# Schematic.net
KiCad netlist of a schematic drawn in Altium Designer
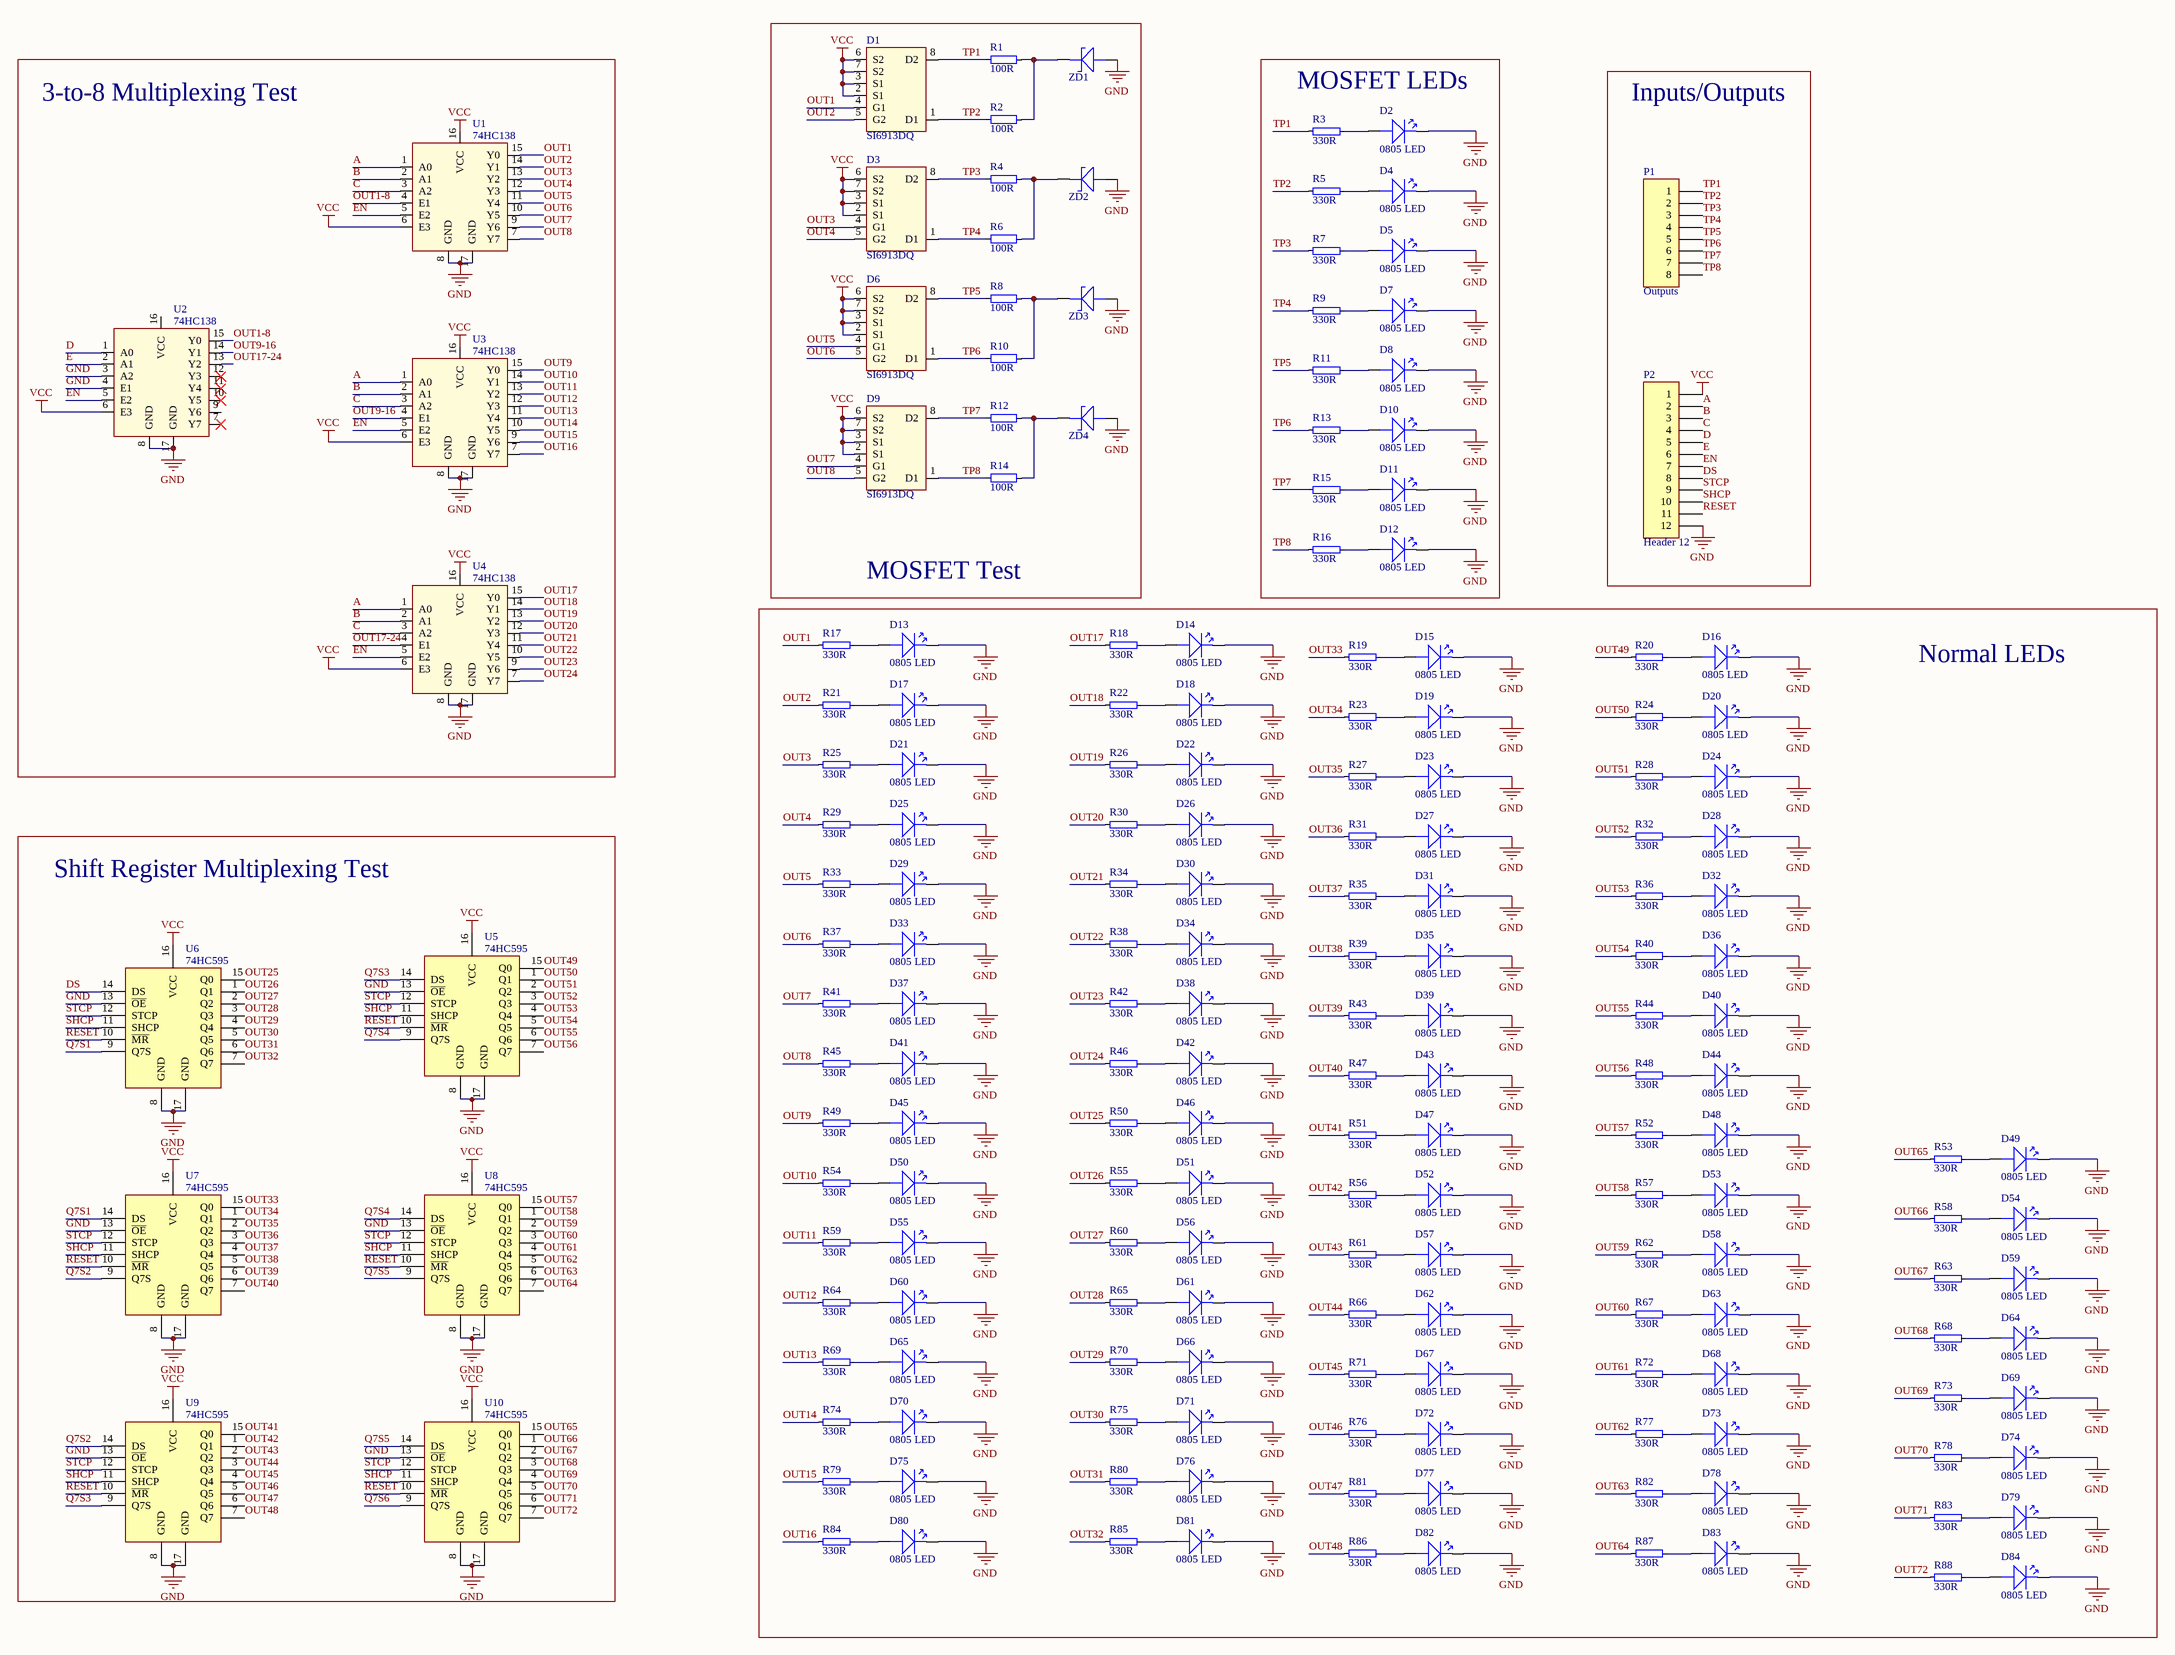
[diagram p0: Schematic.SchDoc]

(export (version "E")
  (design (tool "Eeschema 10.0.6"))
  (components
    (comp (ref "D1")
      (value "SI6913DQ")
      (footprint "Dual Mosfet")
      (libsource (lib "Schlib1") (part "SI6913DQ"))
    )
    (comp (ref "D2") (value "0805 LED") (footprint "0805 LED") (libsource (lib "Schlib1") (part "0805 LED")))
    (comp (ref "D3")
      (value "SI6913DQ")
      (footprint "Dual Mosfet")
      (libsource (lib "Schlib1") (part "SI6913DQ"))
    )
    (comp (ref "D4") (value "0805 LED") (footprint "0805 LED") (libsource (lib "Schlib1") (part "0805 LED")))
    (comp (ref "D5") (value "0805 LED") (footprint "0805 LED") (libsource (lib "Schlib1") (part "0805 LED")))
    (comp (ref "D6")
      (value "SI6913DQ")
      (footprint "Dual Mosfet")
      (libsource (lib "Schlib1") (part "SI6913DQ"))
    )
    (comp (ref "D7") (value "0805 LED") (footprint "0805 LED") (libsource (lib "Schlib1") (part "0805 LED")))
    (comp (ref "D8") (value "0805 LED") (footprint "0805 LED") (libsource (lib "Schlib1") (part "0805 LED")))
    (comp (ref "D9")
      (value "SI6913DQ")
      (footprint "Dual Mosfet")
      (libsource (lib "Schlib1") (part "SI6913DQ"))
    )
    (comp (ref "D10") (value "0805 LED") (footprint "0805 LED") (libsource (lib "Schlib1") (part "0805 LED")))
    (comp (ref "D11") (value "0805 LED") (footprint "0805 LED") (libsource (lib "Schlib1") (part "0805 LED")))
    (comp (ref "D12") (value "0805 LED") (footprint "0805 LED") (libsource (lib "Schlib1") (part "0805 LED")))
    (comp (ref "D13") (value "0805 LED") (footprint "0805 LED") (libsource (lib "Schlib1") (part "0805 LED")))
    (comp (ref "D14") (value "0805 LED") (footprint "0805 LED") (libsource (lib "Schlib1") (part "0805 LED")))
    (comp (ref "D15") (value "0805 LED") (footprint "0805 LED") (libsource (lib "Schlib1") (part "0805 LED")))
    (comp (ref "D16") (value "0805 LED") (footprint "0805 LED") (libsource (lib "Schlib1") (part "0805 LED")))
    (comp (ref "D17") (value "0805 LED") (footprint "0805 LED") (libsource (lib "Schlib1") (part "0805 LED")))
    (comp (ref "D18") (value "0805 LED") (footprint "0805 LED") (libsource (lib "Schlib1") (part "0805 LED")))
    (comp (ref "D19") (value "0805 LED") (footprint "0805 LED") (libsource (lib "Schlib1") (part "0805 LED")))
    (comp (ref "D20") (value "0805 LED") (footprint "0805 LED") (libsource (lib "Schlib1") (part "0805 LED")))
    (comp (ref "D21") (value "0805 LED") (footprint "0805 LED") (libsource (lib "Schlib1") (part "0805 LED")))
    (comp (ref "D22") (value "0805 LED") (footprint "0805 LED") (libsource (lib "Schlib1") (part "0805 LED")))
    (comp (ref "D23") (value "0805 LED") (footprint "0805 LED") (libsource (lib "Schlib1") (part "0805 LED")))
    (comp (ref "D24") (value "0805 LED") (footprint "0805 LED") (libsource (lib "Schlib1") (part "0805 LED")))
    (comp (ref "D25") (value "0805 LED") (footprint "0805 LED") (libsource (lib "Schlib1") (part "0805 LED")))
    (comp (ref "D26") (value "0805 LED") (footprint "0805 LED") (libsource (lib "Schlib1") (part "0805 LED")))
    (comp (ref "D27") (value "0805 LED") (footprint "0805 LED") (libsource (lib "Schlib1") (part "0805 LED")))
    (comp (ref "D28") (value "0805 LED") (footprint "0805 LED") (libsource (lib "Schlib1") (part "0805 LED")))
    (comp (ref "D29") (value "0805 LED") (footprint "0805 LED") (libsource (lib "Schlib1") (part "0805 LED")))
    (comp (ref "D30") (value "0805 LED") (footprint "0805 LED") (libsource (lib "Schlib1") (part "0805 LED")))
    (comp (ref "D31") (value "0805 LED") (footprint "0805 LED") (libsource (lib "Schlib1") (part "0805 LED")))
    (comp (ref "D32") (value "0805 LED") (footprint "0805 LED") (libsource (lib "Schlib1") (part "0805 LED")))
    (comp (ref "D33") (value "0805 LED") (footprint "0805 LED") (libsource (lib "Schlib1") (part "0805 LED")))
    (comp (ref "D34") (value "0805 LED") (footprint "0805 LED") (libsource (lib "Schlib1") (part "0805 LED")))
    (comp (ref "D35") (value "0805 LED") (footprint "0805 LED") (libsource (lib "Schlib1") (part "0805 LED")))
    (comp (ref "D36") (value "0805 LED") (footprint "0805 LED") (libsource (lib "Schlib1") (part "0805 LED")))
    (comp (ref "D37") (value "0805 LED") (footprint "0805 LED") (libsource (lib "Schlib1") (part "0805 LED")))
    (comp (ref "D38") (value "0805 LED") (footprint "0805 LED") (libsource (lib "Schlib1") (part "0805 LED")))
    (comp (ref "D39") (value "0805 LED") (footprint "0805 LED") (libsource (lib "Schlib1") (part "0805 LED")))
    (comp (ref "D40") (value "0805 LED") (footprint "0805 LED") (libsource (lib "Schlib1") (part "0805 LED")))
    (comp (ref "D41") (value "0805 LED") (footprint "0805 LED") (libsource (lib "Schlib1") (part "0805 LED")))
    (comp (ref "D42") (value "0805 LED") (footprint "0805 LED") (libsource (lib "Schlib1") (part "0805 LED")))
    (comp (ref "D43") (value "0805 LED") (footprint "0805 LED") (libsource (lib "Schlib1") (part "0805 LED")))
    (comp (ref "D44") (value "0805 LED") (footprint "0805 LED") (libsource (lib "Schlib1") (part "0805 LED")))
    (comp (ref "D45") (value "0805 LED") (footprint "0805 LED") (libsource (lib "Schlib1") (part "0805 LED")))
    (comp (ref "D46") (value "0805 LED") (footprint "0805 LED") (libsource (lib "Schlib1") (part "0805 LED")))
    (comp (ref "D47") (value "0805 LED") (footprint "0805 LED") (libsource (lib "Schlib1") (part "0805 LED")))
    (comp (ref "D48") (value "0805 LED") (footprint "0805 LED") (libsource (lib "Schlib1") (part "0805 LED")))
    (comp (ref "D49") (value "0805 LED") (footprint "0805 LED") (libsource (lib "Schlib1") (part "0805 LED")))
    (comp (ref "D50") (value "0805 LED") (footprint "0805 LED") (libsource (lib "Schlib1") (part "0805 LED")))
    (comp (ref "D51") (value "0805 LED") (footprint "0805 LED") (libsource (lib "Schlib1") (part "0805 LED")))
    (comp (ref "D52") (value "0805 LED") (footprint "0805 LED") (libsource (lib "Schlib1") (part "0805 LED")))
    (comp (ref "D53") (value "0805 LED") (footprint "0805 LED") (libsource (lib "Schlib1") (part "0805 LED")))
    (comp (ref "D54") (value "0805 LED") (footprint "0805 LED") (libsource (lib "Schlib1") (part "0805 LED")))
    (comp (ref "D55") (value "0805 LED") (footprint "0805 LED") (libsource (lib "Schlib1") (part "0805 LED")))
    (comp (ref "D56") (value "0805 LED") (footprint "0805 LED") (libsource (lib "Schlib1") (part "0805 LED")))
    (comp (ref "D57") (value "0805 LED") (footprint "0805 LED") (libsource (lib "Schlib1") (part "0805 LED")))
    (comp (ref "D58") (value "0805 LED") (footprint "0805 LED") (libsource (lib "Schlib1") (part "0805 LED")))
    (comp (ref "D59") (value "0805 LED") (footprint "0805 LED") (libsource (lib "Schlib1") (part "0805 LED")))
    (comp (ref "D60") (value "0805 LED") (footprint "0805 LED") (libsource (lib "Schlib1") (part "0805 LED")))
    (comp (ref "D61") (value "0805 LED") (footprint "0805 LED") (libsource (lib "Schlib1") (part "0805 LED")))
    (comp (ref "D62") (value "0805 LED") (footprint "0805 LED") (libsource (lib "Schlib1") (part "0805 LED")))
    (comp (ref "D63") (value "0805 LED") (footprint "0805 LED") (libsource (lib "Schlib1") (part "0805 LED")))
    (comp (ref "D64") (value "0805 LED") (footprint "0805 LED") (libsource (lib "Schlib1") (part "0805 LED")))
    (comp (ref "D65") (value "0805 LED") (footprint "0805 LED") (libsource (lib "Schlib1") (part "0805 LED")))
    (comp (ref "D66") (value "0805 LED") (footprint "0805 LED") (libsource (lib "Schlib1") (part "0805 LED")))
    (comp (ref "D67") (value "0805 LED") (footprint "0805 LED") (libsource (lib "Schlib1") (part "0805 LED")))
    (comp (ref "D68") (value "0805 LED") (footprint "0805 LED") (libsource (lib "Schlib1") (part "0805 LED")))
    (comp (ref "D69") (value "0805 LED") (footprint "0805 LED") (libsource (lib "Schlib1") (part "0805 LED")))
    (comp (ref "D70") (value "0805 LED") (footprint "0805 LED") (libsource (lib "Schlib1") (part "0805 LED")))
    (comp (ref "D71") (value "0805 LED") (footprint "0805 LED") (libsource (lib "Schlib1") (part "0805 LED")))
    (comp (ref "D72") (value "0805 LED") (footprint "0805 LED") (libsource (lib "Schlib1") (part "0805 LED")))
    (comp (ref "D73") (value "0805 LED") (footprint "0805 LED") (libsource (lib "Schlib1") (part "0805 LED")))
    (comp (ref "D74") (value "0805 LED") (footprint "0805 LED") (libsource (lib "Schlib1") (part "0805 LED")))
    (comp (ref "D75") (value "0805 LED") (footprint "0805 LED") (libsource (lib "Schlib1") (part "0805 LED")))
    (comp (ref "D76") (value "0805 LED") (footprint "0805 LED") (libsource (lib "Schlib1") (part "0805 LED")))
    (comp (ref "D77") (value "0805 LED") (footprint "0805 LED") (libsource (lib "Schlib1") (part "0805 LED")))
    (comp (ref "D78") (value "0805 LED") (footprint "0805 LED") (libsource (lib "Schlib1") (part "0805 LED")))
    (comp (ref "D79") (value "0805 LED") (footprint "0805 LED") (libsource (lib "Schlib1") (part "0805 LED")))
    (comp (ref "D80") (value "0805 LED") (footprint "0805 LED") (libsource (lib "Schlib1") (part "0805 LED")))
    (comp (ref "D81") (value "0805 LED") (footprint "0805 LED") (libsource (lib "Schlib1") (part "0805 LED")))
    (comp (ref "D82") (value "0805 LED") (footprint "0805 LED") (libsource (lib "Schlib1") (part "0805 LED")))
    (comp (ref "D83") (value "0805 LED") (footprint "0805 LED") (libsource (lib "Schlib1") (part "0805 LED")))
    (comp (ref "D84") (value "0805 LED") (footprint "0805 LED") (libsource (lib "Schlib1") (part "0805 LED")))
    (comp (ref "P1")
      (value "Outputs")
      (footprint "HDR1X8")
      (description "Header, 8-Pin")
      (fields (field (name "PUBLISHER") "Altium Limited"))
      (libsource (lib "Miscellaneous Connectors") (part "Header 8"))
    )
    (comp (ref "P2")
      (value "Header 12")
      (footprint "HDR1X12")
      (description "Header, 12-Pin")
      (fields (field (name "PUBLISHER") "Altium Limited"))
      (libsource (lib "Miscellaneous Connectors") (part "Header 12"))
    )
    (comp (ref "R1")
      (value "100R")
      (footprint "0805 Resistor")
      (libsource (lib "Schlib1") (part "0805 Resistor"))
    )
    (comp (ref "R2")
      (value "100R")
      (footprint "0805 Resistor")
      (libsource (lib "Schlib1") (part "0805 Resistor"))
    )
    (comp (ref "R3")
      (value "330R")
      (footprint "0805 Resistor")
      (libsource (lib "Schlib1") (part "0805 Resistor"))
    )
    (comp (ref "R4")
      (value "100R")
      (footprint "0805 Resistor")
      (libsource (lib "Schlib1") (part "0805 Resistor"))
    )
    (comp (ref "R5")
      (value "330R")
      (footprint "0805 Resistor")
      (libsource (lib "Schlib1") (part "0805 Resistor"))
    )
    (comp (ref "R6")
      (value "100R")
      (footprint "0805 Resistor")
      (libsource (lib "Schlib1") (part "0805 Resistor"))
    )
    (comp (ref "R7")
      (value "330R")
      (footprint "0805 Resistor")
      (libsource (lib "Schlib1") (part "0805 Resistor"))
    )
    (comp (ref "R8")
      (value "100R")
      (footprint "0805 Resistor")
      (libsource (lib "Schlib1") (part "0805 Resistor"))
    )
    (comp (ref "R9")
      (value "330R")
      (footprint "0805 Resistor")
      (libsource (lib "Schlib1") (part "0805 Resistor"))
    )
    (comp (ref "R10")
      (value "100R")
      (footprint "0805 Resistor")
      (libsource (lib "Schlib1") (part "0805 Resistor"))
    )
    (comp (ref "R11")
      (value "330R")
      (footprint "0805 Resistor")
      (libsource (lib "Schlib1") (part "0805 Resistor"))
    )
    (comp (ref "R12")
      (value "100R")
      (footprint "0805 Resistor")
      (libsource (lib "Schlib1") (part "0805 Resistor"))
    )
    (comp (ref "R13")
      (value "330R")
      (footprint "0805 Resistor")
      (libsource (lib "Schlib1") (part "0805 Resistor"))
    )
    (comp (ref "R14")
      (value "100R")
      (footprint "0805 Resistor")
      (libsource (lib "Schlib1") (part "0805 Resistor"))
    )
    (comp (ref "R15")
      (value "330R")
      (footprint "0805 Resistor")
      (libsource (lib "Schlib1") (part "0805 Resistor"))
    )
    (comp (ref "R16")
      (value "330R")
      (footprint "0805 Resistor")
      (libsource (lib "Schlib1") (part "0805 Resistor"))
    )
    (comp (ref "R17")
      (value "330R")
      (footprint "0805 Resistor")
      (libsource (lib "Schlib1") (part "0805 Resistor"))
    )
    (comp (ref "R18")
      (value "330R")
      (footprint "0805 Resistor")
      (libsource (lib "Schlib1") (part "0805 Resistor"))
    )
    (comp (ref "R19")
      (value "330R")
      (footprint "0805 Resistor")
      (libsource (lib "Schlib1") (part "0805 Resistor"))
    )
    (comp (ref "R20")
      (value "330R")
      (footprint "0805 Resistor")
      (libsource (lib "Schlib1") (part "0805 Resistor"))
    )
    (comp (ref "R21")
      (value "330R")
      (footprint "0805 Resistor")
      (libsource (lib "Schlib1") (part "0805 Resistor"))
    )
    (comp (ref "R22")
      (value "330R")
      (footprint "0805 Resistor")
      (libsource (lib "Schlib1") (part "0805 Resistor"))
    )
    (comp (ref "R23")
      (value "330R")
      (footprint "0805 Resistor")
      (libsource (lib "Schlib1") (part "0805 Resistor"))
    )
    (comp (ref "R24")
      (value "330R")
      (footprint "0805 Resistor")
      (libsource (lib "Schlib1") (part "0805 Resistor"))
    )
    (comp (ref "R25")
      (value "330R")
      (footprint "0805 Resistor")
      (libsource (lib "Schlib1") (part "0805 Resistor"))
    )
    (comp (ref "R26")
      (value "330R")
      (footprint "0805 Resistor")
      (libsource (lib "Schlib1") (part "0805 Resistor"))
    )
    (comp (ref "R27")
      (value "330R")
      (footprint "0805 Resistor")
      (libsource (lib "Schlib1") (part "0805 Resistor"))
    )
    (comp (ref "R28")
      (value "330R")
      (footprint "0805 Resistor")
      (libsource (lib "Schlib1") (part "0805 Resistor"))
    )
    (comp (ref "R29")
      (value "330R")
      (footprint "0805 Resistor")
      (libsource (lib "Schlib1") (part "0805 Resistor"))
    )
    (comp (ref "R30")
      (value "330R")
      (footprint "0805 Resistor")
      (libsource (lib "Schlib1") (part "0805 Resistor"))
    )
    (comp (ref "R31")
      (value "330R")
      (footprint "0805 Resistor")
      (libsource (lib "Schlib1") (part "0805 Resistor"))
    )
    (comp (ref "R32")
      (value "330R")
      (footprint "0805 Resistor")
      (libsource (lib "Schlib1") (part "0805 Resistor"))
    )
    (comp (ref "R33")
      (value "330R")
      (footprint "0805 Resistor")
      (libsource (lib "Schlib1") (part "0805 Resistor"))
    )
    (comp (ref "R34")
      (value "330R")
      (footprint "0805 Resistor")
      (libsource (lib "Schlib1") (part "0805 Resistor"))
    )
    (comp (ref "R35")
      (value "330R")
      (footprint "0805 Resistor")
      (libsource (lib "Schlib1") (part "0805 Resistor"))
    )
    (comp (ref "R36")
      (value "330R")
      (footprint "0805 Resistor")
      (libsource (lib "Schlib1") (part "0805 Resistor"))
    )
    (comp (ref "R37")
      (value "330R")
      (footprint "0805 Resistor")
      (libsource (lib "Schlib1") (part "0805 Resistor"))
    )
    (comp (ref "R38")
      (value "330R")
      (footprint "0805 Resistor")
      (libsource (lib "Schlib1") (part "0805 Resistor"))
    )
    (comp (ref "R39")
      (value "330R")
      (footprint "0805 Resistor")
      (libsource (lib "Schlib1") (part "0805 Resistor"))
    )
    (comp (ref "R40")
      (value "330R")
      (footprint "0805 Resistor")
      (libsource (lib "Schlib1") (part "0805 Resistor"))
    )
    (comp (ref "R41")
      (value "330R")
      (footprint "0805 Resistor")
      (libsource (lib "Schlib1") (part "0805 Resistor"))
    )
    (comp (ref "R42")
      (value "330R")
      (footprint "0805 Resistor")
      (libsource (lib "Schlib1") (part "0805 Resistor"))
    )
    (comp (ref "R43")
      (value "330R")
      (footprint "0805 Resistor")
      (libsource (lib "Schlib1") (part "0805 Resistor"))
    )
    (comp (ref "R44")
      (value "330R")
      (footprint "0805 Resistor")
      (libsource (lib "Schlib1") (part "0805 Resistor"))
    )
    (comp (ref "R45")
      (value "330R")
      (footprint "0805 Resistor")
      (libsource (lib "Schlib1") (part "0805 Resistor"))
    )
    (comp (ref "R46")
      (value "330R")
      (footprint "0805 Resistor")
      (libsource (lib "Schlib1") (part "0805 Resistor"))
    )
    (comp (ref "R47")
      (value "330R")
      (footprint "0805 Resistor")
      (libsource (lib "Schlib1") (part "0805 Resistor"))
    )
    (comp (ref "R48")
      (value "330R")
      (footprint "0805 Resistor")
      (libsource (lib "Schlib1") (part "0805 Resistor"))
    )
    (comp (ref "R49")
      (value "330R")
      (footprint "0805 Resistor")
      (libsource (lib "Schlib1") (part "0805 Resistor"))
    )
    (comp (ref "R50")
      (value "330R")
      (footprint "0805 Resistor")
      (libsource (lib "Schlib1") (part "0805 Resistor"))
    )
    (comp (ref "R51")
      (value "330R")
      (footprint "0805 Resistor")
      (libsource (lib "Schlib1") (part "0805 Resistor"))
    )
    (comp (ref "R52")
      (value "330R")
      (footprint "0805 Resistor")
      (libsource (lib "Schlib1") (part "0805 Resistor"))
    )
    (comp (ref "R53")
      (value "330R")
      (footprint "0805 Resistor")
      (libsource (lib "Schlib1") (part "0805 Resistor"))
    )
    (comp (ref "R54")
      (value "330R")
      (footprint "0805 Resistor")
      (libsource (lib "Schlib1") (part "0805 Resistor"))
    )
    (comp (ref "R55")
      (value "330R")
      (footprint "0805 Resistor")
      (libsource (lib "Schlib1") (part "0805 Resistor"))
    )
    (comp (ref "R56")
      (value "330R")
      (footprint "0805 Resistor")
      (libsource (lib "Schlib1") (part "0805 Resistor"))
    )
    (comp (ref "R57")
      (value "330R")
      (footprint "0805 Resistor")
      (libsource (lib "Schlib1") (part "0805 Resistor"))
    )
    (comp (ref "R58")
      (value "330R")
      (footprint "0805 Resistor")
      (libsource (lib "Schlib1") (part "0805 Resistor"))
    )
    (comp (ref "R59")
      (value "330R")
      (footprint "0805 Resistor")
      (libsource (lib "Schlib1") (part "0805 Resistor"))
    )
    (comp (ref "R60")
      (value "330R")
      (footprint "0805 Resistor")
      (libsource (lib "Schlib1") (part "0805 Resistor"))
    )
    (comp (ref "R61")
      (value "330R")
      (footprint "0805 Resistor")
      (libsource (lib "Schlib1") (part "0805 Resistor"))
    )
    (comp (ref "R62")
      (value "330R")
      (footprint "0805 Resistor")
      (libsource (lib "Schlib1") (part "0805 Resistor"))
    )
    (comp (ref "R63")
      (value "330R")
      (footprint "0805 Resistor")
      (libsource (lib "Schlib1") (part "0805 Resistor"))
    )
    (comp (ref "R64")
      (value "330R")
      (footprint "0805 Resistor")
      (libsource (lib "Schlib1") (part "0805 Resistor"))
    )
    (comp (ref "R65")
      (value "330R")
      (footprint "0805 Resistor")
      (libsource (lib "Schlib1") (part "0805 Resistor"))
    )
    (comp (ref "R66")
      (value "330R")
      (footprint "0805 Resistor")
      (libsource (lib "Schlib1") (part "0805 Resistor"))
    )
    (comp (ref "R67")
      (value "330R")
      (footprint "0805 Resistor")
      (libsource (lib "Schlib1") (part "0805 Resistor"))
    )
    (comp (ref "R68")
      (value "330R")
      (footprint "0805 Resistor")
      (libsource (lib "Schlib1") (part "0805 Resistor"))
    )
    (comp (ref "R69")
      (value "330R")
      (footprint "0805 Resistor")
      (libsource (lib "Schlib1") (part "0805 Resistor"))
    )
    (comp (ref "R70")
      (value "330R")
      (footprint "0805 Resistor")
      (libsource (lib "Schlib1") (part "0805 Resistor"))
    )
    (comp (ref "R71")
      (value "330R")
      (footprint "0805 Resistor")
      (libsource (lib "Schlib1") (part "0805 Resistor"))
    )
    (comp (ref "R72")
      (value "330R")
      (footprint "0805 Resistor")
      (libsource (lib "Schlib1") (part "0805 Resistor"))
    )
    (comp (ref "R73")
      (value "330R")
      (footprint "0805 Resistor")
      (libsource (lib "Schlib1") (part "0805 Resistor"))
    )
    (comp (ref "R74")
      (value "330R")
      (footprint "0805 Resistor")
      (libsource (lib "Schlib1") (part "0805 Resistor"))
    )
    (comp (ref "R75")
      (value "330R")
      (footprint "0805 Resistor")
      (libsource (lib "Schlib1") (part "0805 Resistor"))
    )
    (comp (ref "R76")
      (value "330R")
      (footprint "0805 Resistor")
      (libsource (lib "Schlib1") (part "0805 Resistor"))
    )
    (comp (ref "R77")
      (value "330R")
      (footprint "0805 Resistor")
      (libsource (lib "Schlib1") (part "0805 Resistor"))
    )
    (comp (ref "R78")
      (value "330R")
      (footprint "0805 Resistor")
      (libsource (lib "Schlib1") (part "0805 Resistor"))
    )
    (comp (ref "R79")
      (value "330R")
      (footprint "0805 Resistor")
      (libsource (lib "Schlib1") (part "0805 Resistor"))
    )
    (comp (ref "R80")
      (value "330R")
      (footprint "0805 Resistor")
      (libsource (lib "Schlib1") (part "0805 Resistor"))
    )
    (comp (ref "R81")
      (value "330R")
      (footprint "0805 Resistor")
      (libsource (lib "Schlib1") (part "0805 Resistor"))
    )
    (comp (ref "R82")
      (value "330R")
      (footprint "0805 Resistor")
      (libsource (lib "Schlib1") (part "0805 Resistor"))
    )
    (comp (ref "R83")
      (value "330R")
      (footprint "0805 Resistor")
      (libsource (lib "Schlib1") (part "0805 Resistor"))
    )
    (comp (ref "R84")
      (value "330R")
      (footprint "0805 Resistor")
      (libsource (lib "Schlib1") (part "0805 Resistor"))
    )
    (comp (ref "R85")
      (value "330R")
      (footprint "0805 Resistor")
      (libsource (lib "Schlib1") (part "0805 Resistor"))
    )
    (comp (ref "R86")
      (value "330R")
      (footprint "0805 Resistor")
      (libsource (lib "Schlib1") (part "0805 Resistor"))
    )
    (comp (ref "R87")
      (value "330R")
      (footprint "0805 Resistor")
      (libsource (lib "Schlib1") (part "0805 Resistor"))
    )
    (comp (ref "R88")
      (value "330R")
      (footprint "0805 Resistor")
      (libsource (lib "Schlib1") (part "0805 Resistor"))
    )
    (comp (ref "U1") (value "74HC138") (footprint "74HC595") (libsource (lib "Schlib1") (part "74HC138")))
    (comp (ref "U2") (value "74HC138") (footprint "74HC595") (libsource (lib "Schlib1") (part "74HC138")))
    (comp (ref "U3") (value "74HC138") (footprint "74HC595") (libsource (lib "Schlib1") (part "74HC138")))
    (comp (ref "U4") (value "74HC138") (footprint "74HC595") (libsource (lib "Schlib1") (part "74HC138")))
    (comp (ref "U5") (value "74HC595") (footprint "74HC595") (libsource (lib "Schlib1") (part "74HC595")))
    (comp (ref "U6") (value "74HC595") (footprint "74HC595") (libsource (lib "Schlib1") (part "74HC595")))
    (comp (ref "U7") (value "74HC595") (footprint "74HC595") (libsource (lib "Schlib1") (part "74HC595")))
    (comp (ref "U8") (value "74HC595") (footprint "74HC595") (libsource (lib "Schlib1") (part "74HC595")))
    (comp (ref "U9") (value "74HC595") (footprint "74HC595") (libsource (lib "Schlib1") (part "74HC595")))
    (comp (ref "U10") (value "74HC595") (footprint "74HC595") (libsource (lib "Schlib1") (part "74HC595")))
    (comp (ref "ZD1") (value "3V") (footprint "Zener Diode") (libsource (lib "Schlib1") (part "BZV55-C3V0")))
    (comp (ref "ZD2") (value "3V") (footprint "Zener Diode") (libsource (lib "Schlib1") (part "BZV55-C3V0")))
    (comp (ref "ZD3") (value "3V") (footprint "Zener Diode") (libsource (lib "Schlib1") (part "BZV55-C3V0")))
    (comp (ref "ZD4") (value "3V") (footprint "Zener Diode") (libsource (lib "Schlib1") (part "BZV55-C3V0")))
  )
  (nets
    (net (code "1") (name "/A") (class "Default")
      (node (ref "P2") (pin "2") (pinfunction "2_2") (pintype "passive"))
      (node (ref "U1") (pin "1") (pinfunction "A0_1") (pintype "passive"))
      (node (ref "U3") (pin "1") (pinfunction "A0_1") (pintype "passive"))
      (node (ref "U4") (pin "1") (pinfunction "A0_1") (pintype "passive"))
    )
    (net (code "2") (name "/B") (class "Default")
      (node (ref "P2") (pin "3") (pinfunction "3_3") (pintype "passive"))
      (node (ref "U1") (pin "2") (pinfunction "A1_2") (pintype "passive"))
      (node (ref "U3") (pin "2") (pinfunction "A1_2") (pintype "passive"))
      (node (ref "U4") (pin "2") (pinfunction "A1_2") (pintype "passive"))
    )
    (net (code "3") (name "/C") (class "Default")
      (node (ref "P2") (pin "4") (pinfunction "4_4") (pintype "passive"))
      (node (ref "U1") (pin "3") (pinfunction "A2_3") (pintype "passive"))
      (node (ref "U3") (pin "3") (pinfunction "A2_3") (pintype "passive"))
      (node (ref "U4") (pin "3") (pinfunction "A2_3") (pintype "passive"))
    )
    (net (code "4") (name "/D") (class "Default")
      (node (ref "P2") (pin "5") (pinfunction "5_5") (pintype "passive"))
      (node (ref "U2") (pin "1") (pinfunction "A0_1") (pintype "passive"))
    )
    (net (code "5") (name "/DS") (class "Default")
      (node (ref "P2") (pin "8") (pinfunction "8_8") (pintype "passive"))
      (node (ref "U6") (pin "14") (pinfunction "DS_14") (pintype "passive"))
    )
    (net (code "6") (name "/E") (class "Default")
      (node (ref "P2") (pin "6") (pinfunction "6_6") (pintype "passive"))
      (node (ref "U2") (pin "2") (pinfunction "A1_2") (pintype "passive"))
    )
    (net (code "7") (name "/EN") (class "Default")
      (node (ref "P2") (pin "7") (pinfunction "7_7") (pintype "passive"))
      (node (ref "U1") (pin "5") (pinfunction "E2_5") (pintype "passive"))
      (node (ref "U2") (pin "5") (pinfunction "E2_5") (pintype "passive"))
      (node (ref "U3") (pin "5") (pinfunction "E2_5") (pintype "passive"))
      (node (ref "U4") (pin "5") (pinfunction "E2_5") (pintype "passive"))
    )
    (net (code "8") (name "/OUT1") (class "Default")
      (node (ref "D1") (pin "4") (pinfunction "G1_4") (pintype "passive"))
      (node (ref "R17") (pin "2") (pinfunction "2_2") (pintype "passive"))
      (node (ref "U1") (pin "15") (pinfunction "Y0_15") (pintype "passive"))
    )
    (net (code "9") (name "/OUT1-8") (class "Default")
      (node (ref "U1") (pin "4") (pinfunction "E1_4") (pintype "passive"))
      (node (ref "U2") (pin "15") (pinfunction "Y0_15") (pintype "passive"))
    )
    (net (code "10") (name "/OUT2") (class "Default")
      (node (ref "D1") (pin "5") (pinfunction "G2_5") (pintype "passive"))
      (node (ref "R21") (pin "2") (pinfunction "2_2") (pintype "passive"))
      (node (ref "U1") (pin "14") (pinfunction "Y1_14") (pintype "passive"))
    )
    (net (code "11") (name "/OUT3") (class "Default")
      (node (ref "D3") (pin "4") (pinfunction "G1_4") (pintype "passive"))
      (node (ref "R25") (pin "2") (pinfunction "2_2") (pintype "passive"))
      (node (ref "U1") (pin "13") (pinfunction "Y2_13") (pintype "passive"))
    )
    (net (code "12") (name "/OUT4") (class "Default")
      (node (ref "D3") (pin "5") (pinfunction "G2_5") (pintype "passive"))
      (node (ref "R29") (pin "2") (pinfunction "2_2") (pintype "passive"))
      (node (ref "U1") (pin "12") (pinfunction "Y3_12") (pintype "passive"))
    )
    (net (code "13") (name "/OUT5") (class "Default")
      (node (ref "D6") (pin "4") (pinfunction "G1_4") (pintype "passive"))
      (node (ref "R33") (pin "2") (pinfunction "2_2") (pintype "passive"))
      (node (ref "U1") (pin "11") (pinfunction "Y4_11") (pintype "passive"))
    )
    (net (code "14") (name "/OUT6") (class "Default")
      (node (ref "D6") (pin "5") (pinfunction "G2_5") (pintype "passive"))
      (node (ref "R37") (pin "2") (pinfunction "2_2") (pintype "passive"))
      (node (ref "U1") (pin "10") (pinfunction "Y5_10") (pintype "passive"))
    )
    (net (code "15") (name "/OUT7") (class "Default")
      (node (ref "D9") (pin "4") (pinfunction "G1_4") (pintype "passive"))
      (node (ref "R41") (pin "2") (pinfunction "2_2") (pintype "passive"))
      (node (ref "U1") (pin "9") (pinfunction "Y6_9") (pintype "passive"))
    )
    (net (code "16") (name "/OUT8") (class "Default")
      (node (ref "D9") (pin "5") (pinfunction "G2_5") (pintype "passive"))
      (node (ref "R45") (pin "2") (pinfunction "2_2") (pintype "passive"))
      (node (ref "U1") (pin "7") (pinfunction "Y7_7") (pintype "passive"))
    )
    (net (code "17") (name "/OUT9") (class "Default")
      (node (ref "R49") (pin "2") (pinfunction "2_2") (pintype "passive"))
      (node (ref "U3") (pin "15") (pinfunction "Y0_15") (pintype "passive"))
    )
    (net (code "18") (name "/OUT9-16") (class "Default")
      (node (ref "U2") (pin "14") (pinfunction "Y1_14") (pintype "passive"))
      (node (ref "U3") (pin "4") (pinfunction "E1_4") (pintype "passive"))
    )
    (net (code "19") (name "/OUT10") (class "Default")
      (node (ref "R54") (pin "2") (pinfunction "2_2") (pintype "passive"))
      (node (ref "U3") (pin "14") (pinfunction "Y1_14") (pintype "passive"))
    )
    (net (code "20") (name "/OUT11") (class "Default")
      (node (ref "R59") (pin "2") (pinfunction "2_2") (pintype "passive"))
      (node (ref "U3") (pin "13") (pinfunction "Y2_13") (pintype "passive"))
    )
    (net (code "21") (name "/OUT12") (class "Default")
      (node (ref "R64") (pin "2") (pinfunction "2_2") (pintype "passive"))
      (node (ref "U3") (pin "12") (pinfunction "Y3_12") (pintype "passive"))
    )
    (net (code "22") (name "/OUT13") (class "Default")
      (node (ref "R69") (pin "2") (pinfunction "2_2") (pintype "passive"))
      (node (ref "U3") (pin "11") (pinfunction "Y4_11") (pintype "passive"))
    )
    (net (code "23") (name "/OUT14") (class "Default")
      (node (ref "R74") (pin "2") (pinfunction "2_2") (pintype "passive"))
      (node (ref "U3") (pin "10") (pinfunction "Y5_10") (pintype "passive"))
    )
    (net (code "24") (name "/OUT15") (class "Default")
      (node (ref "R79") (pin "2") (pinfunction "2_2") (pintype "passive"))
      (node (ref "U3") (pin "9") (pinfunction "Y6_9") (pintype "passive"))
    )
    (net (code "25") (name "/OUT16") (class "Default")
      (node (ref "R84") (pin "2") (pinfunction "2_2") (pintype "passive"))
      (node (ref "U3") (pin "7") (pinfunction "Y7_7") (pintype "passive"))
    )
    (net (code "26") (name "/OUT17") (class "Default")
      (node (ref "R18") (pin "2") (pinfunction "2_2") (pintype "passive"))
      (node (ref "U4") (pin "15") (pinfunction "Y0_15") (pintype "passive"))
    )
    (net (code "27") (name "/OUT17-24") (class "Default")
      (node (ref "U2") (pin "13") (pinfunction "Y2_13") (pintype "passive"))
      (node (ref "U4") (pin "4") (pinfunction "E1_4") (pintype "passive"))
    )
    (net (code "28") (name "/OUT18") (class "Default")
      (node (ref "R22") (pin "2") (pinfunction "2_2") (pintype "passive"))
      (node (ref "U4") (pin "14") (pinfunction "Y1_14") (pintype "passive"))
    )
    (net (code "29") (name "/OUT19") (class "Default")
      (node (ref "R26") (pin "2") (pinfunction "2_2") (pintype "passive"))
      (node (ref "U4") (pin "13") (pinfunction "Y2_13") (pintype "passive"))
    )
    (net (code "30") (name "/OUT20") (class "Default")
      (node (ref "R30") (pin "2") (pinfunction "2_2") (pintype "passive"))
      (node (ref "U4") (pin "12") (pinfunction "Y3_12") (pintype "passive"))
    )
    (net (code "31") (name "/OUT21") (class "Default")
      (node (ref "R34") (pin "2") (pinfunction "2_2") (pintype "passive"))
      (node (ref "U4") (pin "11") (pinfunction "Y4_11") (pintype "passive"))
    )
    (net (code "32") (name "/OUT22") (class "Default")
      (node (ref "R38") (pin "2") (pinfunction "2_2") (pintype "passive"))
      (node (ref "U4") (pin "10") (pinfunction "Y5_10") (pintype "passive"))
    )
    (net (code "33") (name "/OUT23") (class "Default")
      (node (ref "R42") (pin "2") (pinfunction "2_2") (pintype "passive"))
      (node (ref "U4") (pin "9") (pinfunction "Y6_9") (pintype "passive"))
    )
    (net (code "34") (name "/OUT24") (class "Default")
      (node (ref "R46") (pin "2") (pinfunction "2_2") (pintype "passive"))
      (node (ref "U4") (pin "7") (pinfunction "Y7_7") (pintype "passive"))
    )
    (net (code "35") (name "/OUT25") (class "Default")
      (node (ref "R50") (pin "2") (pinfunction "2_2") (pintype "passive"))
      (node (ref "U6") (pin "15") (pinfunction "Q0_15") (pintype "passive"))
    )
    (net (code "36") (name "/OUT26") (class "Default")
      (node (ref "R55") (pin "2") (pinfunction "2_2") (pintype "passive"))
      (node (ref "U6") (pin "1") (pinfunction "Q1_1") (pintype "passive"))
    )
    (net (code "37") (name "/OUT27") (class "Default")
      (node (ref "R60") (pin "2") (pinfunction "2_2") (pintype "passive"))
      (node (ref "U6") (pin "2") (pinfunction "Q2_2") (pintype "passive"))
    )
    (net (code "38") (name "/OUT28") (class "Default")
      (node (ref "R65") (pin "2") (pinfunction "2_2") (pintype "passive"))
      (node (ref "U6") (pin "3") (pinfunction "Q3_3") (pintype "passive"))
    )
    (net (code "39") (name "/OUT29") (class "Default")
      (node (ref "R70") (pin "2") (pinfunction "2_2") (pintype "passive"))
      (node (ref "U6") (pin "4") (pinfunction "Q4_4") (pintype "passive"))
    )
    (net (code "40") (name "/OUT30") (class "Default")
      (node (ref "R75") (pin "2") (pinfunction "2_2") (pintype "passive"))
      (node (ref "U6") (pin "5") (pinfunction "Q5_5") (pintype "passive"))
    )
    (net (code "41") (name "/OUT31") (class "Default")
      (node (ref "R80") (pin "2") (pinfunction "2_2") (pintype "passive"))
      (node (ref "U6") (pin "6") (pinfunction "Q6_6") (pintype "passive"))
    )
    (net (code "42") (name "/OUT32") (class "Default")
      (node (ref "R85") (pin "2") (pinfunction "2_2") (pintype "passive"))
      (node (ref "U6") (pin "7") (pinfunction "Q7_7") (pintype "passive"))
    )
    (net (code "43") (name "/OUT33") (class "Default")
      (node (ref "R19") (pin "2") (pinfunction "2_2") (pintype "passive"))
      (node (ref "U7") (pin "15") (pinfunction "Q0_15") (pintype "passive"))
    )
    (net (code "44") (name "/OUT34") (class "Default")
      (node (ref "R23") (pin "2") (pinfunction "2_2") (pintype "passive"))
      (node (ref "U7") (pin "1") (pinfunction "Q1_1") (pintype "passive"))
    )
    (net (code "45") (name "/OUT35") (class "Default")
      (node (ref "R27") (pin "2") (pinfunction "2_2") (pintype "passive"))
      (node (ref "U7") (pin "2") (pinfunction "Q2_2") (pintype "passive"))
    )
    (net (code "46") (name "/OUT36") (class "Default")
      (node (ref "R31") (pin "2") (pinfunction "2_2") (pintype "passive"))
      (node (ref "U7") (pin "3") (pinfunction "Q3_3") (pintype "passive"))
    )
    (net (code "47") (name "/OUT37") (class "Default")
      (node (ref "R35") (pin "2") (pinfunction "2_2") (pintype "passive"))
      (node (ref "U7") (pin "4") (pinfunction "Q4_4") (pintype "passive"))
    )
    (net (code "48") (name "/OUT38") (class "Default")
      (node (ref "R39") (pin "2") (pinfunction "2_2") (pintype "passive"))
      (node (ref "U7") (pin "5") (pinfunction "Q5_5") (pintype "passive"))
    )
    (net (code "49") (name "/OUT39") (class "Default")
      (node (ref "R43") (pin "2") (pinfunction "2_2") (pintype "passive"))
      (node (ref "U7") (pin "6") (pinfunction "Q6_6") (pintype "passive"))
    )
    (net (code "50") (name "/OUT40") (class "Default")
      (node (ref "R47") (pin "2") (pinfunction "2_2") (pintype "passive"))
      (node (ref "U7") (pin "7") (pinfunction "Q7_7") (pintype "passive"))
    )
    (net (code "51") (name "/OUT41") (class "Default")
      (node (ref "R51") (pin "2") (pinfunction "2_2") (pintype "passive"))
      (node (ref "U9") (pin "15") (pinfunction "Q0_15") (pintype "passive"))
    )
    (net (code "52") (name "/OUT42") (class "Default")
      (node (ref "R56") (pin "2") (pinfunction "2_2") (pintype "passive"))
      (node (ref "U9") (pin "1") (pinfunction "Q1_1") (pintype "passive"))
    )
    (net (code "53") (name "/OUT43") (class "Default")
      (node (ref "R61") (pin "2") (pinfunction "2_2") (pintype "passive"))
      (node (ref "U9") (pin "2") (pinfunction "Q2_2") (pintype "passive"))
    )
    (net (code "54") (name "/OUT44") (class "Default")
      (node (ref "R66") (pin "2") (pinfunction "2_2") (pintype "passive"))
      (node (ref "U9") (pin "3") (pinfunction "Q3_3") (pintype "passive"))
    )
    (net (code "55") (name "/OUT45") (class "Default")
      (node (ref "R71") (pin "2") (pinfunction "2_2") (pintype "passive"))
      (node (ref "U9") (pin "4") (pinfunction "Q4_4") (pintype "passive"))
    )
    (net (code "56") (name "/OUT46") (class "Default")
      (node (ref "R76") (pin "2") (pinfunction "2_2") (pintype "passive"))
      (node (ref "U9") (pin "5") (pinfunction "Q5_5") (pintype "passive"))
    )
    (net (code "57") (name "/OUT47") (class "Default")
      (node (ref "R81") (pin "2") (pinfunction "2_2") (pintype "passive"))
      (node (ref "U9") (pin "6") (pinfunction "Q6_6") (pintype "passive"))
    )
    (net (code "58") (name "/OUT48") (class "Default")
      (node (ref "R86") (pin "2") (pinfunction "2_2") (pintype "passive"))
      (node (ref "U9") (pin "7") (pinfunction "Q7_7") (pintype "passive"))
    )
    (net (code "59") (name "/OUT49") (class "Default")
      (node (ref "R20") (pin "2") (pinfunction "2_2") (pintype "passive"))
      (node (ref "U5") (pin "15") (pinfunction "Q0_15") (pintype "passive"))
    )
    (net (code "60") (name "/OUT50") (class "Default")
      (node (ref "R24") (pin "2") (pinfunction "2_2") (pintype "passive"))
      (node (ref "U5") (pin "1") (pinfunction "Q1_1") (pintype "passive"))
    )
    (net (code "61") (name "/OUT51") (class "Default")
      (node (ref "R28") (pin "2") (pinfunction "2_2") (pintype "passive"))
      (node (ref "U5") (pin "2") (pinfunction "Q2_2") (pintype "passive"))
    )
    (net (code "62") (name "/OUT52") (class "Default")
      (node (ref "R32") (pin "2") (pinfunction "2_2") (pintype "passive"))
      (node (ref "U5") (pin "3") (pinfunction "Q3_3") (pintype "passive"))
    )
    (net (code "63") (name "/OUT53") (class "Default")
      (node (ref "R36") (pin "2") (pinfunction "2_2") (pintype "passive"))
      (node (ref "U5") (pin "4") (pinfunction "Q4_4") (pintype "passive"))
    )
    (net (code "64") (name "/OUT54") (class "Default")
      (node (ref "R40") (pin "2") (pinfunction "2_2") (pintype "passive"))
      (node (ref "U5") (pin "5") (pinfunction "Q5_5") (pintype "passive"))
    )
    (net (code "65") (name "/OUT55") (class "Default")
      (node (ref "R44") (pin "2") (pinfunction "2_2") (pintype "passive"))
      (node (ref "U5") (pin "6") (pinfunction "Q6_6") (pintype "passive"))
    )
    (net (code "66") (name "/OUT56") (class "Default")
      (node (ref "R48") (pin "2") (pinfunction "2_2") (pintype "passive"))
      (node (ref "U5") (pin "7") (pinfunction "Q7_7") (pintype "passive"))
    )
    (net (code "67") (name "/OUT57") (class "Default")
      (node (ref "R52") (pin "2") (pinfunction "2_2") (pintype "passive"))
      (node (ref "U8") (pin "15") (pinfunction "Q0_15") (pintype "passive"))
    )
    (net (code "68") (name "/OUT58") (class "Default")
      (node (ref "R57") (pin "2") (pinfunction "2_2") (pintype "passive"))
      (node (ref "U8") (pin "1") (pinfunction "Q1_1") (pintype "passive"))
    )
    (net (code "69") (name "/OUT59") (class "Default")
      (node (ref "R62") (pin "2") (pinfunction "2_2") (pintype "passive"))
      (node (ref "U8") (pin "2") (pinfunction "Q2_2") (pintype "passive"))
    )
    (net (code "70") (name "/OUT60") (class "Default")
      (node (ref "R67") (pin "2") (pinfunction "2_2") (pintype "passive"))
      (node (ref "U8") (pin "3") (pinfunction "Q3_3") (pintype "passive"))
    )
    (net (code "71") (name "/OUT61") (class "Default")
      (node (ref "R72") (pin "2") (pinfunction "2_2") (pintype "passive"))
      (node (ref "U8") (pin "4") (pinfunction "Q4_4") (pintype "passive"))
    )
    (net (code "72") (name "/OUT62") (class "Default")
      (node (ref "R77") (pin "2") (pinfunction "2_2") (pintype "passive"))
      (node (ref "U8") (pin "5") (pinfunction "Q5_5") (pintype "passive"))
    )
    (net (code "73") (name "/OUT63") (class "Default")
      (node (ref "R82") (pin "2") (pinfunction "2_2") (pintype "passive"))
      (node (ref "U8") (pin "6") (pinfunction "Q6_6") (pintype "passive"))
    )
    (net (code "74") (name "/OUT64") (class "Default")
      (node (ref "R87") (pin "2") (pinfunction "2_2") (pintype "passive"))
      (node (ref "U8") (pin "7") (pinfunction "Q7_7") (pintype "passive"))
    )
    (net (code "75") (name "/OUT65") (class "Default")
      (node (ref "R53") (pin "2") (pinfunction "2_2") (pintype "passive"))
      (node (ref "U10") (pin "15") (pinfunction "Q0_15") (pintype "passive"))
    )
    (net (code "76") (name "/OUT66") (class "Default")
      (node (ref "R58") (pin "2") (pinfunction "2_2") (pintype "passive"))
      (node (ref "U10") (pin "1") (pinfunction "Q1_1") (pintype "passive"))
    )
    (net (code "77") (name "/OUT67") (class "Default")
      (node (ref "R63") (pin "2") (pinfunction "2_2") (pintype "passive"))
      (node (ref "U10") (pin "2") (pinfunction "Q2_2") (pintype "passive"))
    )
    (net (code "78") (name "/OUT68") (class "Default")
      (node (ref "R68") (pin "2") (pinfunction "2_2") (pintype "passive"))
      (node (ref "U10") (pin "3") (pinfunction "Q3_3") (pintype "passive"))
    )
    (net (code "79") (name "/OUT69") (class "Default")
      (node (ref "R73") (pin "2") (pinfunction "2_2") (pintype "passive"))
      (node (ref "U10") (pin "4") (pinfunction "Q4_4") (pintype "passive"))
    )
    (net (code "80") (name "/OUT70") (class "Default")
      (node (ref "R78") (pin "2") (pinfunction "2_2") (pintype "passive"))
      (node (ref "U10") (pin "5") (pinfunction "Q5_5") (pintype "passive"))
    )
    (net (code "81") (name "/OUT71") (class "Default")
      (node (ref "R83") (pin "2") (pinfunction "2_2") (pintype "passive"))
      (node (ref "U10") (pin "6") (pinfunction "Q6_6") (pintype "passive"))
    )
    (net (code "82") (name "/OUT72") (class "Default")
      (node (ref "R88") (pin "2") (pinfunction "2_2") (pintype "passive"))
      (node (ref "U10") (pin "7") (pinfunction "Q7_7") (pintype "passive"))
    )
    (net (code "83") (name "/Q7S1") (class "Default")
      (node (ref "U6") (pin "9") (pinfunction "Q7S_9") (pintype "passive"))
      (node (ref "U7") (pin "14") (pinfunction "DS_14") (pintype "passive"))
    )
    (net (code "84") (name "/Q7S2") (class "Default")
      (node (ref "U7") (pin "9") (pinfunction "Q7S_9") (pintype "passive"))
      (node (ref "U9") (pin "14") (pinfunction "DS_14") (pintype "passive"))
    )
    (net (code "85") (name "/Q7S3") (class "Default")
      (node (ref "U5") (pin "14") (pinfunction "DS_14") (pintype "passive"))
      (node (ref "U9") (pin "9") (pinfunction "Q7S_9") (pintype "passive"))
    )
    (net (code "86") (name "/Q7S4") (class "Default")
      (node (ref "U5") (pin "9") (pinfunction "Q7S_9") (pintype "passive"))
      (node (ref "U8") (pin "14") (pinfunction "DS_14") (pintype "passive"))
    )
    (net (code "87") (name "/Q7S5") (class "Default")
      (node (ref "U10") (pin "14") (pinfunction "DS_14") (pintype "passive"))
      (node (ref "U8") (pin "9") (pinfunction "Q7S_9") (pintype "passive"))
    )
    (net (code "88") (name "/Q7S6") (class "Default")
      (node (ref "U10") (pin "9") (pinfunction "Q7S_9") (pintype "passive"))
    )
    (net (code "89") (name "/RESET") (class "Default")
      (node (ref "P2") (pin "11") (pinfunction "11_11") (pintype "passive"))
      (node (ref "U10") (pin "10") (pinfunction "~{MR}_10") (pintype "passive"))
      (node (ref "U5") (pin "10") (pinfunction "~{MR}_10") (pintype "passive"))
      (node (ref "U6") (pin "10") (pinfunction "~{MR}_10") (pintype "passive"))
      (node (ref "U7") (pin "10") (pinfunction "~{MR}_10") (pintype "passive"))
      (node (ref "U8") (pin "10") (pinfunction "~{MR}_10") (pintype "passive"))
      (node (ref "U9") (pin "10") (pinfunction "~{MR}_10") (pintype "passive"))
    )
    (net (code "90") (name "/SHCP") (class "Default")
      (node (ref "P2") (pin "10") (pinfunction "10_10") (pintype "passive"))
      (node (ref "U10") (pin "11") (pinfunction "SHCP_11") (pintype "passive"))
      (node (ref "U5") (pin "11") (pinfunction "SHCP_11") (pintype "passive"))
      (node (ref "U6") (pin "11") (pinfunction "SHCP_11") (pintype "passive"))
      (node (ref "U7") (pin "11") (pinfunction "SHCP_11") (pintype "passive"))
      (node (ref "U8") (pin "11") (pinfunction "SHCP_11") (pintype "passive"))
      (node (ref "U9") (pin "11") (pinfunction "SHCP_11") (pintype "passive"))
    )
    (net (code "91") (name "/STCP") (class "Default")
      (node (ref "P2") (pin "9") (pinfunction "9_9") (pintype "passive"))
      (node (ref "U10") (pin "12") (pinfunction "STCP_12") (pintype "passive"))
      (node (ref "U5") (pin "12") (pinfunction "STCP_12") (pintype "passive"))
      (node (ref "U6") (pin "12") (pinfunction "STCP_12") (pintype "passive"))
      (node (ref "U7") (pin "12") (pinfunction "STCP_12") (pintype "passive"))
      (node (ref "U8") (pin "12") (pinfunction "STCP_12") (pintype "passive"))
      (node (ref "U9") (pin "12") (pinfunction "STCP_12") (pintype "passive"))
    )
    (net (code "92") (name "/TP1") (class "Default")
      (node (ref "D1") (pin "8") (pinfunction "D2_8") (pintype "passive"))
      (node (ref "P1") (pin "1") (pinfunction "1_1") (pintype "passive"))
      (node (ref "R1") (pin "1") (pinfunction "1_1") (pintype "passive"))
      (node (ref "R3") (pin "2") (pinfunction "2_2") (pintype "passive"))
    )
    (net (code "93") (name "/TP2") (class "Default")
      (node (ref "D1") (pin "1") (pinfunction "D1_1") (pintype "passive"))
      (node (ref "P1") (pin "2") (pinfunction "2_2") (pintype "passive"))
      (node (ref "R2") (pin "1") (pinfunction "1_1") (pintype "passive"))
      (node (ref "R5") (pin "2") (pinfunction "2_2") (pintype "passive"))
    )
    (net (code "94") (name "/TP3") (class "Default")
      (node (ref "D3") (pin "8") (pinfunction "D2_8") (pintype "passive"))
      (node (ref "P1") (pin "3") (pinfunction "3_3") (pintype "passive"))
      (node (ref "R4") (pin "1") (pinfunction "1_1") (pintype "passive"))
      (node (ref "R7") (pin "2") (pinfunction "2_2") (pintype "passive"))
    )
    (net (code "95") (name "/TP4") (class "Default")
      (node (ref "D3") (pin "1") (pinfunction "D1_1") (pintype "passive"))
      (node (ref "P1") (pin "4") (pinfunction "4_4") (pintype "passive"))
      (node (ref "R6") (pin "1") (pinfunction "1_1") (pintype "passive"))
      (node (ref "R9") (pin "2") (pinfunction "2_2") (pintype "passive"))
    )
    (net (code "96") (name "/TP5") (class "Default")
      (node (ref "D6") (pin "8") (pinfunction "D2_8") (pintype "passive"))
      (node (ref "P1") (pin "5") (pinfunction "5_5") (pintype "passive"))
      (node (ref "R11") (pin "2") (pinfunction "2_2") (pintype "passive"))
      (node (ref "R8") (pin "1") (pinfunction "1_1") (pintype "passive"))
    )
    (net (code "97") (name "/TP6") (class "Default")
      (node (ref "D6") (pin "1") (pinfunction "D1_1") (pintype "passive"))
      (node (ref "P1") (pin "6") (pinfunction "6_6") (pintype "passive"))
      (node (ref "R10") (pin "1") (pinfunction "1_1") (pintype "passive"))
      (node (ref "R13") (pin "2") (pinfunction "2_2") (pintype "passive"))
    )
    (net (code "98") (name "/TP7") (class "Default")
      (node (ref "D9") (pin "8") (pinfunction "D2_8") (pintype "passive"))
      (node (ref "P1") (pin "7") (pinfunction "7_7") (pintype "passive"))
      (node (ref "R12") (pin "1") (pinfunction "1_1") (pintype "passive"))
      (node (ref "R15") (pin "2") (pinfunction "2_2") (pintype "passive"))
    )
    (net (code "99") (name "/TP8") (class "Default")
      (node (ref "D9") (pin "1") (pinfunction "D1_1") (pintype "passive"))
      (node (ref "P1") (pin "8") (pinfunction "8_8") (pintype "passive"))
      (node (ref "R14") (pin "1") (pinfunction "1_1") (pintype "passive"))
      (node (ref "R16") (pin "2") (pinfunction "2_2") (pintype "passive"))
    )
    (net (code "100") (name "GND") (class "Default")
      (node (ref "D10") (pin "1") (pinfunction "1_1") (pintype "passive"))
      (node (ref "D11") (pin "1") (pinfunction "1_1") (pintype "passive"))
      (node (ref "D12") (pin "1") (pinfunction "1_1") (pintype "passive"))
      (node (ref "D13") (pin "1") (pinfunction "1_1") (pintype "passive"))
      (node (ref "D14") (pin "1") (pinfunction "1_1") (pintype "passive"))
      (node (ref "D15") (pin "1") (pinfunction "1_1") (pintype "passive"))
      (node (ref "D16") (pin "1") (pinfunction "1_1") (pintype "passive"))
      (node (ref "D17") (pin "1") (pinfunction "1_1") (pintype "passive"))
      (node (ref "D18") (pin "1") (pinfunction "1_1") (pintype "passive"))
      (node (ref "D19") (pin "1") (pinfunction "1_1") (pintype "passive"))
      (node (ref "D2") (pin "1") (pinfunction "1_1") (pintype "passive"))
      (node (ref "D20") (pin "1") (pinfunction "1_1") (pintype "passive"))
      (node (ref "D21") (pin "1") (pinfunction "1_1") (pintype "passive"))
      (node (ref "D22") (pin "1") (pinfunction "1_1") (pintype "passive"))
      (node (ref "D23") (pin "1") (pinfunction "1_1") (pintype "passive"))
      (node (ref "D24") (pin "1") (pinfunction "1_1") (pintype "passive"))
      (node (ref "D25") (pin "1") (pinfunction "1_1") (pintype "passive"))
      (node (ref "D26") (pin "1") (pinfunction "1_1") (pintype "passive"))
      (node (ref "D27") (pin "1") (pinfunction "1_1") (pintype "passive"))
      (node (ref "D28") (pin "1") (pinfunction "1_1") (pintype "passive"))
      (node (ref "D29") (pin "1") (pinfunction "1_1") (pintype "passive"))
      (node (ref "D30") (pin "1") (pinfunction "1_1") (pintype "passive"))
      (node (ref "D31") (pin "1") (pinfunction "1_1") (pintype "passive"))
      (node (ref "D32") (pin "1") (pinfunction "1_1") (pintype "passive"))
      (node (ref "D33") (pin "1") (pinfunction "1_1") (pintype "passive"))
      (node (ref "D34") (pin "1") (pinfunction "1_1") (pintype "passive"))
      (node (ref "D35") (pin "1") (pinfunction "1_1") (pintype "passive"))
      (node (ref "D36") (pin "1") (pinfunction "1_1") (pintype "passive"))
      (node (ref "D37") (pin "1") (pinfunction "1_1") (pintype "passive"))
      (node (ref "D38") (pin "1") (pinfunction "1_1") (pintype "passive"))
      (node (ref "D39") (pin "1") (pinfunction "1_1") (pintype "passive"))
      (node (ref "D4") (pin "1") (pinfunction "1_1") (pintype "passive"))
      (node (ref "D40") (pin "1") (pinfunction "1_1") (pintype "passive"))
      (node (ref "D41") (pin "1") (pinfunction "1_1") (pintype "passive"))
      (node (ref "D42") (pin "1") (pinfunction "1_1") (pintype "passive"))
      (node (ref "D43") (pin "1") (pinfunction "1_1") (pintype "passive"))
      (node (ref "D44") (pin "1") (pinfunction "1_1") (pintype "passive"))
      (node (ref "D45") (pin "1") (pinfunction "1_1") (pintype "passive"))
      (node (ref "D46") (pin "1") (pinfunction "1_1") (pintype "passive"))
      (node (ref "D47") (pin "1") (pinfunction "1_1") (pintype "passive"))
      (node (ref "D48") (pin "1") (pinfunction "1_1") (pintype "passive"))
      (node (ref "D49") (pin "1") (pinfunction "1_1") (pintype "passive"))
      (node (ref "D5") (pin "1") (pinfunction "1_1") (pintype "passive"))
      (node (ref "D50") (pin "1") (pinfunction "1_1") (pintype "passive"))
      (node (ref "D51") (pin "1") (pinfunction "1_1") (pintype "passive"))
      (node (ref "D52") (pin "1") (pinfunction "1_1") (pintype "passive"))
      (node (ref "D53") (pin "1") (pinfunction "1_1") (pintype "passive"))
      (node (ref "D54") (pin "1") (pinfunction "1_1") (pintype "passive"))
      (node (ref "D55") (pin "1") (pinfunction "1_1") (pintype "passive"))
      (node (ref "D56") (pin "1") (pinfunction "1_1") (pintype "passive"))
      (node (ref "D57") (pin "1") (pinfunction "1_1") (pintype "passive"))
      (node (ref "D58") (pin "1") (pinfunction "1_1") (pintype "passive"))
      (node (ref "D59") (pin "1") (pinfunction "1_1") (pintype "passive"))
      (node (ref "D60") (pin "1") (pinfunction "1_1") (pintype "passive"))
      (node (ref "D61") (pin "1") (pinfunction "1_1") (pintype "passive"))
      (node (ref "D62") (pin "1") (pinfunction "1_1") (pintype "passive"))
      (node (ref "D63") (pin "1") (pinfunction "1_1") (pintype "passive"))
      (node (ref "D64") (pin "1") (pinfunction "1_1") (pintype "passive"))
      (node (ref "D65") (pin "1") (pinfunction "1_1") (pintype "passive"))
      (node (ref "D66") (pin "1") (pinfunction "1_1") (pintype "passive"))
      (node (ref "D67") (pin "1") (pinfunction "1_1") (pintype "passive"))
      (node (ref "D68") (pin "1") (pinfunction "1_1") (pintype "passive"))
      (node (ref "D69") (pin "1") (pinfunction "1_1") (pintype "passive"))
      (node (ref "D7") (pin "1") (pinfunction "1_1") (pintype "passive"))
      (node (ref "D70") (pin "1") (pinfunction "1_1") (pintype "passive"))
      (node (ref "D71") (pin "1") (pinfunction "1_1") (pintype "passive"))
      (node (ref "D72") (pin "1") (pinfunction "1_1") (pintype "passive"))
      (node (ref "D73") (pin "1") (pinfunction "1_1") (pintype "passive"))
      (node (ref "D74") (pin "1") (pinfunction "1_1") (pintype "passive"))
      (node (ref "D75") (pin "1") (pinfunction "1_1") (pintype "passive"))
      (node (ref "D76") (pin "1") (pinfunction "1_1") (pintype "passive"))
      (node (ref "D77") (pin "1") (pinfunction "1_1") (pintype "passive"))
      (node (ref "D78") (pin "1") (pinfunction "1_1") (pintype "passive"))
      (node (ref "D79") (pin "1") (pinfunction "1_1") (pintype "passive"))
      (node (ref "D8") (pin "1") (pinfunction "1_1") (pintype "passive"))
      (node (ref "D80") (pin "1") (pinfunction "1_1") (pintype "passive"))
      (node (ref "D81") (pin "1") (pinfunction "1_1") (pintype "passive"))
      (node (ref "D82") (pin "1") (pinfunction "1_1") (pintype "passive"))
      (node (ref "D83") (pin "1") (pinfunction "1_1") (pintype "passive"))
      (node (ref "D84") (pin "1") (pinfunction "1_1") (pintype "passive"))
      (node (ref "P2") (pin "12") (pinfunction "12_12") (pintype "passive"))
      (node (ref "U1") (pin "17") (pinfunction "GND_17") (pintype "passive"))
      (node (ref "U1") (pin "8") (pinfunction "GND_8") (pintype "passive"))
      (node (ref "U10") (pin "13") (pinfunction "~{OE}_13") (pintype "passive"))
      (node (ref "U10") (pin "17") (pinfunction "GND_17") (pintype "passive"))
      (node (ref "U10") (pin "8") (pinfunction "GND_8") (pintype "passive"))
      (node (ref "U2") (pin "17") (pinfunction "GND_17") (pintype "passive"))
      (node (ref "U2") (pin "3") (pinfunction "A2_3") (pintype "passive"))
      (node (ref "U2") (pin "4") (pinfunction "E1_4") (pintype "passive"))
      (node (ref "U2") (pin "8") (pinfunction "GND_8") (pintype "passive"))
      (node (ref "U3") (pin "17") (pinfunction "GND_17") (pintype "passive"))
      (node (ref "U3") (pin "8") (pinfunction "GND_8") (pintype "passive"))
      (node (ref "U4") (pin "17") (pinfunction "GND_17") (pintype "passive"))
      (node (ref "U4") (pin "8") (pinfunction "GND_8") (pintype "passive"))
      (node (ref "U5") (pin "13") (pinfunction "~{OE}_13") (pintype "passive"))
      (node (ref "U5") (pin "17") (pinfunction "GND_17") (pintype "passive"))
      (node (ref "U5") (pin "8") (pinfunction "GND_8") (pintype "passive"))
      (node (ref "U6") (pin "13") (pinfunction "~{OE}_13") (pintype "passive"))
      (node (ref "U6") (pin "17") (pinfunction "GND_17") (pintype "passive"))
      (node (ref "U6") (pin "8") (pinfunction "GND_8") (pintype "passive"))
      (node (ref "U7") (pin "13") (pinfunction "~{OE}_13") (pintype "passive"))
      (node (ref "U7") (pin "17") (pinfunction "GND_17") (pintype "passive"))
      (node (ref "U7") (pin "8") (pinfunction "GND_8") (pintype "passive"))
      (node (ref "U8") (pin "13") (pinfunction "~{OE}_13") (pintype "passive"))
      (node (ref "U8") (pin "17") (pinfunction "GND_17") (pintype "passive"))
      (node (ref "U8") (pin "8") (pinfunction "GND_8") (pintype "passive"))
      (node (ref "U9") (pin "13") (pinfunction "~{OE}_13") (pintype "passive"))
      (node (ref "U9") (pin "17") (pinfunction "GND_17") (pintype "passive"))
      (node (ref "U9") (pin "8") (pinfunction "GND_8") (pintype "passive"))
      (node (ref "ZD1") (pin "2") (pinfunction "2_2") (pintype "passive"))
      (node (ref "ZD2") (pin "2") (pinfunction "2_2") (pintype "passive"))
      (node (ref "ZD3") (pin "2") (pinfunction "2_2") (pintype "passive"))
      (node (ref "ZD4") (pin "2") (pinfunction "2_2") (pintype "passive"))
    )
    (net (code "101") (name "Net-(D2-Pad2)") (class "Default")
      (node (ref "D2") (pin "2") (pinfunction "2_2") (pintype "passive"))
      (node (ref "R3") (pin "1") (pinfunction "1_1") (pintype "passive"))
    )
    (net (code "102") (name "Net-(D4-Pad2)") (class "Default")
      (node (ref "D4") (pin "2") (pinfunction "2_2") (pintype "passive"))
      (node (ref "R5") (pin "1") (pinfunction "1_1") (pintype "passive"))
    )
    (net (code "103") (name "Net-(D5-Pad2)") (class "Default")
      (node (ref "D5") (pin "2") (pinfunction "2_2") (pintype "passive"))
      (node (ref "R7") (pin "1") (pinfunction "1_1") (pintype "passive"))
    )
    (net (code "104") (name "Net-(D7-Pad2)") (class "Default")
      (node (ref "D7") (pin "2") (pinfunction "2_2") (pintype "passive"))
      (node (ref "R9") (pin "1") (pinfunction "1_1") (pintype "passive"))
    )
    (net (code "105") (name "Net-(D8-Pad2)") (class "Default")
      (node (ref "D8") (pin "2") (pinfunction "2_2") (pintype "passive"))
      (node (ref "R11") (pin "1") (pinfunction "1_1") (pintype "passive"))
    )
    (net (code "106") (name "Net-(D10-Pad2)") (class "Default")
      (node (ref "D10") (pin "2") (pinfunction "2_2") (pintype "passive"))
      (node (ref "R13") (pin "1") (pinfunction "1_1") (pintype "passive"))
    )
    (net (code "107") (name "Net-(D11-Pad2)") (class "Default")
      (node (ref "D11") (pin "2") (pinfunction "2_2") (pintype "passive"))
      (node (ref "R15") (pin "1") (pinfunction "1_1") (pintype "passive"))
    )
    (net (code "108") (name "Net-(D12-Pad2)") (class "Default")
      (node (ref "D12") (pin "2") (pinfunction "2_2") (pintype "passive"))
      (node (ref "R16") (pin "1") (pinfunction "1_1") (pintype "passive"))
    )
    (net (code "109") (name "Net-(D13-Pad2)") (class "Default")
      (node (ref "D13") (pin "2") (pinfunction "2_2") (pintype "passive"))
      (node (ref "R17") (pin "1") (pinfunction "1_1") (pintype "passive"))
    )
    (net (code "110") (name "Net-(D14-Pad2)") (class "Default")
      (node (ref "D14") (pin "2") (pinfunction "2_2") (pintype "passive"))
      (node (ref "R18") (pin "1") (pinfunction "1_1") (pintype "passive"))
    )
    (net (code "111") (name "Net-(D15-Pad2)") (class "Default")
      (node (ref "D15") (pin "2") (pinfunction "2_2") (pintype "passive"))
      (node (ref "R19") (pin "1") (pinfunction "1_1") (pintype "passive"))
    )
    (net (code "112") (name "Net-(D16-Pad2)") (class "Default")
      (node (ref "D16") (pin "2") (pinfunction "2_2") (pintype "passive"))
      (node (ref "R20") (pin "1") (pinfunction "1_1") (pintype "passive"))
    )
    (net (code "113") (name "Net-(D17-Pad2)") (class "Default")
      (node (ref "D17") (pin "2") (pinfunction "2_2") (pintype "passive"))
      (node (ref "R21") (pin "1") (pinfunction "1_1") (pintype "passive"))
    )
    (net (code "114") (name "Net-(D18-Pad2)") (class "Default")
      (node (ref "D18") (pin "2") (pinfunction "2_2") (pintype "passive"))
      (node (ref "R22") (pin "1") (pinfunction "1_1") (pintype "passive"))
    )
    (net (code "115") (name "Net-(D19-Pad2)") (class "Default")
      (node (ref "D19") (pin "2") (pinfunction "2_2") (pintype "passive"))
      (node (ref "R23") (pin "1") (pinfunction "1_1") (pintype "passive"))
    )
    (net (code "116") (name "Net-(D20-Pad2)") (class "Default")
      (node (ref "D20") (pin "2") (pinfunction "2_2") (pintype "passive"))
      (node (ref "R24") (pin "1") (pinfunction "1_1") (pintype "passive"))
    )
    (net (code "117") (name "Net-(D21-Pad2)") (class "Default")
      (node (ref "D21") (pin "2") (pinfunction "2_2") (pintype "passive"))
      (node (ref "R25") (pin "1") (pinfunction "1_1") (pintype "passive"))
    )
    (net (code "118") (name "Net-(D22-Pad2)") (class "Default")
      (node (ref "D22") (pin "2") (pinfunction "2_2") (pintype "passive"))
      (node (ref "R26") (pin "1") (pinfunction "1_1") (pintype "passive"))
    )
    (net (code "119") (name "Net-(D23-Pad2)") (class "Default")
      (node (ref "D23") (pin "2") (pinfunction "2_2") (pintype "passive"))
      (node (ref "R27") (pin "1") (pinfunction "1_1") (pintype "passive"))
    )
    (net (code "120") (name "Net-(D24-Pad2)") (class "Default")
      (node (ref "D24") (pin "2") (pinfunction "2_2") (pintype "passive"))
      (node (ref "R28") (pin "1") (pinfunction "1_1") (pintype "passive"))
    )
    (net (code "121") (name "Net-(D25-Pad2)") (class "Default")
      (node (ref "D25") (pin "2") (pinfunction "2_2") (pintype "passive"))
      (node (ref "R29") (pin "1") (pinfunction "1_1") (pintype "passive"))
    )
    (net (code "122") (name "Net-(D26-Pad2)") (class "Default")
      (node (ref "D26") (pin "2") (pinfunction "2_2") (pintype "passive"))
      (node (ref "R30") (pin "1") (pinfunction "1_1") (pintype "passive"))
    )
    (net (code "123") (name "Net-(D27-Pad2)") (class "Default")
      (node (ref "D27") (pin "2") (pinfunction "2_2") (pintype "passive"))
      (node (ref "R31") (pin "1") (pinfunction "1_1") (pintype "passive"))
    )
    (net (code "124") (name "Net-(D28-Pad2)") (class "Default")
      (node (ref "D28") (pin "2") (pinfunction "2_2") (pintype "passive"))
      (node (ref "R32") (pin "1") (pinfunction "1_1") (pintype "passive"))
    )
    (net (code "125") (name "Net-(D29-Pad2)") (class "Default")
      (node (ref "D29") (pin "2") (pinfunction "2_2") (pintype "passive"))
      (node (ref "R33") (pin "1") (pinfunction "1_1") (pintype "passive"))
    )
    (net (code "126") (name "Net-(D30-Pad2)") (class "Default")
      (node (ref "D30") (pin "2") (pinfunction "2_2") (pintype "passive"))
      (node (ref "R34") (pin "1") (pinfunction "1_1") (pintype "passive"))
    )
    (net (code "127") (name "Net-(D31-Pad2)") (class "Default")
      (node (ref "D31") (pin "2") (pinfunction "2_2") (pintype "passive"))
      (node (ref "R35") (pin "1") (pinfunction "1_1") (pintype "passive"))
    )
    (net (code "128") (name "Net-(D32-Pad2)") (class "Default")
      (node (ref "D32") (pin "2") (pinfunction "2_2") (pintype "passive"))
      (node (ref "R36") (pin "1") (pinfunction "1_1") (pintype "passive"))
    )
    (net (code "129") (name "Net-(D33-Pad2)") (class "Default")
      (node (ref "D33") (pin "2") (pinfunction "2_2") (pintype "passive"))
      (node (ref "R37") (pin "1") (pinfunction "1_1") (pintype "passive"))
    )
    (net (code "130") (name "Net-(D34-Pad2)") (class "Default")
      (node (ref "D34") (pin "2") (pinfunction "2_2") (pintype "passive"))
      (node (ref "R38") (pin "1") (pinfunction "1_1") (pintype "passive"))
    )
    (net (code "131") (name "Net-(D35-Pad2)") (class "Default")
      (node (ref "D35") (pin "2") (pinfunction "2_2") (pintype "passive"))
      (node (ref "R39") (pin "1") (pinfunction "1_1") (pintype "passive"))
    )
    (net (code "132") (name "Net-(D36-Pad2)") (class "Default")
      (node (ref "D36") (pin "2") (pinfunction "2_2") (pintype "passive"))
      (node (ref "R40") (pin "1") (pinfunction "1_1") (pintype "passive"))
    )
    (net (code "133") (name "Net-(D37-Pad2)") (class "Default")
      (node (ref "D37") (pin "2") (pinfunction "2_2") (pintype "passive"))
      (node (ref "R41") (pin "1") (pinfunction "1_1") (pintype "passive"))
    )
    (net (code "134") (name "Net-(D38-Pad2)") (class "Default")
      (node (ref "D38") (pin "2") (pinfunction "2_2") (pintype "passive"))
      (node (ref "R42") (pin "1") (pinfunction "1_1") (pintype "passive"))
    )
    (net (code "135") (name "Net-(D39-Pad2)") (class "Default")
      (node (ref "D39") (pin "2") (pinfunction "2_2") (pintype "passive"))
      (node (ref "R43") (pin "1") (pinfunction "1_1") (pintype "passive"))
    )
    (net (code "136") (name "Net-(D40-Pad2)") (class "Default")
      (node (ref "D40") (pin "2") (pinfunction "2_2") (pintype "passive"))
      (node (ref "R44") (pin "1") (pinfunction "1_1") (pintype "passive"))
    )
    (net (code "137") (name "Net-(D41-Pad2)") (class "Default")
      (node (ref "D41") (pin "2") (pinfunction "2_2") (pintype "passive"))
      (node (ref "R45") (pin "1") (pinfunction "1_1") (pintype "passive"))
    )
    (net (code "138") (name "Net-(D42-Pad2)") (class "Default")
      (node (ref "D42") (pin "2") (pinfunction "2_2") (pintype "passive"))
      (node (ref "R46") (pin "1") (pinfunction "1_1") (pintype "passive"))
    )
    (net (code "139") (name "Net-(D43-Pad2)") (class "Default")
      (node (ref "D43") (pin "2") (pinfunction "2_2") (pintype "passive"))
      (node (ref "R47") (pin "1") (pinfunction "1_1") (pintype "passive"))
    )
    (net (code "140") (name "Net-(D44-Pad2)") (class "Default")
      (node (ref "D44") (pin "2") (pinfunction "2_2") (pintype "passive"))
      (node (ref "R48") (pin "1") (pinfunction "1_1") (pintype "passive"))
    )
    (net (code "141") (name "Net-(D45-Pad2)") (class "Default")
      (node (ref "D45") (pin "2") (pinfunction "2_2") (pintype "passive"))
      (node (ref "R49") (pin "1") (pinfunction "1_1") (pintype "passive"))
    )
    (net (code "142") (name "Net-(D46-Pad2)") (class "Default")
      (node (ref "D46") (pin "2") (pinfunction "2_2") (pintype "passive"))
      (node (ref "R50") (pin "1") (pinfunction "1_1") (pintype "passive"))
    )
    (net (code "143") (name "Net-(D47-Pad2)") (class "Default")
      (node (ref "D47") (pin "2") (pinfunction "2_2") (pintype "passive"))
      (node (ref "R51") (pin "1") (pinfunction "1_1") (pintype "passive"))
    )
    (net (code "144") (name "Net-(D48-Pad2)") (class "Default")
      (node (ref "D48") (pin "2") (pinfunction "2_2") (pintype "passive"))
      (node (ref "R52") (pin "1") (pinfunction "1_1") (pintype "passive"))
    )
    (net (code "145") (name "Net-(D49-Pad2)") (class "Default")
      (node (ref "D49") (pin "2") (pinfunction "2_2") (pintype "passive"))
      (node (ref "R53") (pin "1") (pinfunction "1_1") (pintype "passive"))
    )
    (net (code "146") (name "Net-(D50-Pad2)") (class "Default")
      (node (ref "D50") (pin "2") (pinfunction "2_2") (pintype "passive"))
      (node (ref "R54") (pin "1") (pinfunction "1_1") (pintype "passive"))
    )
    (net (code "147") (name "Net-(D51-Pad2)") (class "Default")
      (node (ref "D51") (pin "2") (pinfunction "2_2") (pintype "passive"))
      (node (ref "R55") (pin "1") (pinfunction "1_1") (pintype "passive"))
    )
    (net (code "148") (name "Net-(D52-Pad2)") (class "Default")
      (node (ref "D52") (pin "2") (pinfunction "2_2") (pintype "passive"))
      (node (ref "R56") (pin "1") (pinfunction "1_1") (pintype "passive"))
    )
    (net (code "149") (name "Net-(D53-Pad2)") (class "Default")
      (node (ref "D53") (pin "2") (pinfunction "2_2") (pintype "passive"))
      (node (ref "R57") (pin "1") (pinfunction "1_1") (pintype "passive"))
    )
    (net (code "150") (name "Net-(D54-Pad2)") (class "Default")
      (node (ref "D54") (pin "2") (pinfunction "2_2") (pintype "passive"))
      (node (ref "R58") (pin "1") (pinfunction "1_1") (pintype "passive"))
    )
    (net (code "151") (name "Net-(D55-Pad2)") (class "Default")
      (node (ref "D55") (pin "2") (pinfunction "2_2") (pintype "passive"))
      (node (ref "R59") (pin "1") (pinfunction "1_1") (pintype "passive"))
    )
    (net (code "152") (name "Net-(D56-Pad2)") (class "Default")
      (node (ref "D56") (pin "2") (pinfunction "2_2") (pintype "passive"))
      (node (ref "R60") (pin "1") (pinfunction "1_1") (pintype "passive"))
    )
    (net (code "153") (name "Net-(D57-Pad2)") (class "Default")
      (node (ref "D57") (pin "2") (pinfunction "2_2") (pintype "passive"))
      (node (ref "R61") (pin "1") (pinfunction "1_1") (pintype "passive"))
    )
    (net (code "154") (name "Net-(D58-Pad2)") (class "Default")
      (node (ref "D58") (pin "2") (pinfunction "2_2") (pintype "passive"))
      (node (ref "R62") (pin "1") (pinfunction "1_1") (pintype "passive"))
    )
    (net (code "155") (name "Net-(D59-Pad2)") (class "Default")
      (node (ref "D59") (pin "2") (pinfunction "2_2") (pintype "passive"))
      (node (ref "R63") (pin "1") (pinfunction "1_1") (pintype "passive"))
    )
    (net (code "156") (name "Net-(D60-Pad2)") (class "Default")
      (node (ref "D60") (pin "2") (pinfunction "2_2") (pintype "passive"))
      (node (ref "R64") (pin "1") (pinfunction "1_1") (pintype "passive"))
    )
    (net (code "157") (name "Net-(D61-Pad2)") (class "Default")
      (node (ref "D61") (pin "2") (pinfunction "2_2") (pintype "passive"))
      (node (ref "R65") (pin "1") (pinfunction "1_1") (pintype "passive"))
    )
    (net (code "158") (name "Net-(D62-Pad2)") (class "Default")
      (node (ref "D62") (pin "2") (pinfunction "2_2") (pintype "passive"))
      (node (ref "R66") (pin "1") (pinfunction "1_1") (pintype "passive"))
    )
    (net (code "159") (name "Net-(D63-Pad2)") (class "Default")
      (node (ref "D63") (pin "2") (pinfunction "2_2") (pintype "passive"))
      (node (ref "R67") (pin "1") (pinfunction "1_1") (pintype "passive"))
    )
    (net (code "160") (name "Net-(D64-Pad2)") (class "Default")
      (node (ref "D64") (pin "2") (pinfunction "2_2") (pintype "passive"))
      (node (ref "R68") (pin "1") (pinfunction "1_1") (pintype "passive"))
    )
    (net (code "161") (name "Net-(D65-Pad2)") (class "Default")
      (node (ref "D65") (pin "2") (pinfunction "2_2") (pintype "passive"))
      (node (ref "R69") (pin "1") (pinfunction "1_1") (pintype "passive"))
    )
    (net (code "162") (name "Net-(D66-Pad2)") (class "Default")
      (node (ref "D66") (pin "2") (pinfunction "2_2") (pintype "passive"))
      (node (ref "R70") (pin "1") (pinfunction "1_1") (pintype "passive"))
    )
    (net (code "163") (name "Net-(D67-Pad2)") (class "Default")
      (node (ref "D67") (pin "2") (pinfunction "2_2") (pintype "passive"))
      (node (ref "R71") (pin "1") (pinfunction "1_1") (pintype "passive"))
    )
    (net (code "164") (name "Net-(D68-Pad2)") (class "Default")
      (node (ref "D68") (pin "2") (pinfunction "2_2") (pintype "passive"))
      (node (ref "R72") (pin "1") (pinfunction "1_1") (pintype "passive"))
    )
    (net (code "165") (name "Net-(D69-Pad2)") (class "Default")
      (node (ref "D69") (pin "2") (pinfunction "2_2") (pintype "passive"))
      (node (ref "R73") (pin "1") (pinfunction "1_1") (pintype "passive"))
    )
    (net (code "166") (name "Net-(D70-Pad2)") (class "Default")
      (node (ref "D70") (pin "2") (pinfunction "2_2") (pintype "passive"))
      (node (ref "R74") (pin "1") (pinfunction "1_1") (pintype "passive"))
    )
    (net (code "167") (name "Net-(D71-Pad2)") (class "Default")
      (node (ref "D71") (pin "2") (pinfunction "2_2") (pintype "passive"))
      (node (ref "R75") (pin "1") (pinfunction "1_1") (pintype "passive"))
    )
    (net (code "168") (name "Net-(D72-Pad2)") (class "Default")
      (node (ref "D72") (pin "2") (pinfunction "2_2") (pintype "passive"))
      (node (ref "R76") (pin "1") (pinfunction "1_1") (pintype "passive"))
    )
    (net (code "169") (name "Net-(D73-Pad2)") (class "Default")
      (node (ref "D73") (pin "2") (pinfunction "2_2") (pintype "passive"))
      (node (ref "R77") (pin "1") (pinfunction "1_1") (pintype "passive"))
    )
    (net (code "170") (name "Net-(D74-Pad2)") (class "Default")
      (node (ref "D74") (pin "2") (pinfunction "2_2") (pintype "passive"))
      (node (ref "R78") (pin "1") (pinfunction "1_1") (pintype "passive"))
    )
    (net (code "171") (name "Net-(D75-Pad2)") (class "Default")
      (node (ref "D75") (pin "2") (pinfunction "2_2") (pintype "passive"))
      (node (ref "R79") (pin "1") (pinfunction "1_1") (pintype "passive"))
    )
    (net (code "172") (name "Net-(D76-Pad2)") (class "Default")
      (node (ref "D76") (pin "2") (pinfunction "2_2") (pintype "passive"))
      (node (ref "R80") (pin "1") (pinfunction "1_1") (pintype "passive"))
    )
    (net (code "173") (name "Net-(D77-Pad2)") (class "Default")
      (node (ref "D77") (pin "2") (pinfunction "2_2") (pintype "passive"))
      (node (ref "R81") (pin "1") (pinfunction "1_1") (pintype "passive"))
    )
    (net (code "174") (name "Net-(D78-Pad2)") (class "Default")
      (node (ref "D78") (pin "2") (pinfunction "2_2") (pintype "passive"))
      (node (ref "R82") (pin "1") (pinfunction "1_1") (pintype "passive"))
    )
    (net (code "175") (name "Net-(D79-Pad2)") (class "Default")
      (node (ref "D79") (pin "2") (pinfunction "2_2") (pintype "passive"))
      (node (ref "R83") (pin "1") (pinfunction "1_1") (pintype "passive"))
    )
    (net (code "176") (name "Net-(D80-Pad2)") (class "Default")
      (node (ref "D80") (pin "2") (pinfunction "2_2") (pintype "passive"))
      (node (ref "R84") (pin "1") (pinfunction "1_1") (pintype "passive"))
    )
    (net (code "177") (name "Net-(D81-Pad2)") (class "Default")
      (node (ref "D81") (pin "2") (pinfunction "2_2") (pintype "passive"))
      (node (ref "R85") (pin "1") (pinfunction "1_1") (pintype "passive"))
    )
    (net (code "178") (name "Net-(D82-Pad2)") (class "Default")
      (node (ref "D82") (pin "2") (pinfunction "2_2") (pintype "passive"))
      (node (ref "R86") (pin "1") (pinfunction "1_1") (pintype "passive"))
    )
    (net (code "179") (name "Net-(D83-Pad2)") (class "Default")
      (node (ref "D83") (pin "2") (pinfunction "2_2") (pintype "passive"))
      (node (ref "R87") (pin "1") (pinfunction "1_1") (pintype "passive"))
    )
    (net (code "180") (name "Net-(D84-Pad2)") (class "Default")
      (node (ref "D84") (pin "2") (pinfunction "2_2") (pintype "passive"))
      (node (ref "R88") (pin "1") (pinfunction "1_1") (pintype "passive"))
    )
    (net (code "181") (name "Net-(R1-Pad2)") (class "Default")
      (node (ref "R1") (pin "2") (pinfunction "2_2") (pintype "passive"))
      (node (ref "R2") (pin "2") (pinfunction "2_2") (pintype "passive"))
      (node (ref "ZD1") (pin "1") (pinfunction "1_1") (pintype "passive"))
    )
    (net (code "182") (name "Net-(R4-Pad2)") (class "Default")
      (node (ref "R4") (pin "2") (pinfunction "2_2") (pintype "passive"))
      (node (ref "R6") (pin "2") (pinfunction "2_2") (pintype "passive"))
      (node (ref "ZD2") (pin "1") (pinfunction "1_1") (pintype "passive"))
    )
    (net (code "183") (name "Net-(R10-Pad2)") (class "Default")
      (node (ref "R10") (pin "2") (pinfunction "2_2") (pintype "passive"))
      (node (ref "R8") (pin "2") (pinfunction "2_2") (pintype "passive"))
      (node (ref "ZD3") (pin "1") (pinfunction "1_1") (pintype "passive"))
    )
    (net (code "184") (name "Net-(R12-Pad2)") (class "Default")
      (node (ref "R12") (pin "2") (pinfunction "2_2") (pintype "passive"))
      (node (ref "R14") (pin "2") (pinfunction "2_2") (pintype "passive"))
      (node (ref "ZD4") (pin "1") (pinfunction "1_1") (pintype "passive"))
    )
    (net (code "185") (name "VCC") (class "Default")
      (node (ref "D1") (pin "2") (pinfunction "S1_2") (pintype "passive"))
      (node (ref "D1") (pin "3") (pinfunction "S1_3") (pintype "passive"))
      (node (ref "D1") (pin "6") (pinfunction "S2_6") (pintype "passive"))
      (node (ref "D1") (pin "7") (pinfunction "S2_7") (pintype "passive"))
      (node (ref "D3") (pin "2") (pinfunction "S1_2") (pintype "passive"))
      (node (ref "D3") (pin "3") (pinfunction "S1_3") (pintype "passive"))
      (node (ref "D3") (pin "6") (pinfunction "S2_6") (pintype "passive"))
      (node (ref "D3") (pin "7") (pinfunction "S2_7") (pintype "passive"))
      (node (ref "D6") (pin "2") (pinfunction "S1_2") (pintype "passive"))
      (node (ref "D6") (pin "3") (pinfunction "S1_3") (pintype "passive"))
      (node (ref "D6") (pin "6") (pinfunction "S2_6") (pintype "passive"))
      (node (ref "D6") (pin "7") (pinfunction "S2_7") (pintype "passive"))
      (node (ref "D9") (pin "2") (pinfunction "S1_2") (pintype "passive"))
      (node (ref "D9") (pin "3") (pinfunction "S1_3") (pintype "passive"))
      (node (ref "D9") (pin "6") (pinfunction "S2_6") (pintype "passive"))
      (node (ref "D9") (pin "7") (pinfunction "S2_7") (pintype "passive"))
      (node (ref "P2") (pin "1") (pinfunction "1_1") (pintype "passive"))
      (node (ref "U1") (pin "16") (pinfunction "VCC_16") (pintype "passive"))
      (node (ref "U1") (pin "6") (pinfunction "E3_6") (pintype "passive"))
      (node (ref "U10") (pin "16") (pinfunction "VCC_16") (pintype "passive"))
      (node (ref "U2") (pin "6") (pinfunction "E3_6") (pintype "passive"))
      (node (ref "U3") (pin "16") (pinfunction "VCC_16") (pintype "passive"))
      (node (ref "U3") (pin "6") (pinfunction "E3_6") (pintype "passive"))
      (node (ref "U4") (pin "16") (pinfunction "VCC_16") (pintype "passive"))
      (node (ref "U4") (pin "6") (pinfunction "E3_6") (pintype "passive"))
      (node (ref "U5") (pin "16") (pinfunction "VCC_16") (pintype "passive"))
      (node (ref "U6") (pin "16") (pinfunction "VCC_16") (pintype "passive"))
      (node (ref "U7") (pin "16") (pinfunction "VCC_16") (pintype "passive"))
      (node (ref "U8") (pin "16") (pinfunction "VCC_16") (pintype "passive"))
      (node (ref "U9") (pin "16") (pinfunction "VCC_16") (pintype "passive"))
    )
    (net (code "186") (name "unconnected-(U2-VCC-Pad16)") (class "Default")
      (node (ref "U2") (pin "16") (pinfunction "VCC_16") (pintype "passive"))
    )
    (net (code "187") (name "unconnected-(U2-Y3-Pad12)") (class "Default")
      (node (ref "U2") (pin "12") (pinfunction "Y3_12") (pintype "passive+no_connect"))
    )
    (net (code "188") (name "unconnected-(U2-Y4-Pad11)") (class "Default")
      (node (ref "U2") (pin "11") (pinfunction "Y4_11") (pintype "passive+no_connect"))
    )
    (net (code "189") (name "unconnected-(U2-Y5-Pad10)") (class "Default")
      (node (ref "U2") (pin "10") (pinfunction "Y5_10") (pintype "passive+no_connect"))
    )
    (net (code "190") (name "unconnected-(U2-Y6-Pad9)") (class "Default")
      (node (ref "U2") (pin "9") (pinfunction "Y6_9") (pintype "passive"))
    )
    (net (code "191") (name "unconnected-(U2-Y7-Pad7)") (class "Default")
      (node (ref "U2") (pin "7") (pinfunction "Y7_7") (pintype "passive+no_connect"))
    )
  )
)
